# ElectroLab.net
KiCad netlist of a schematic drawn in EAGLE
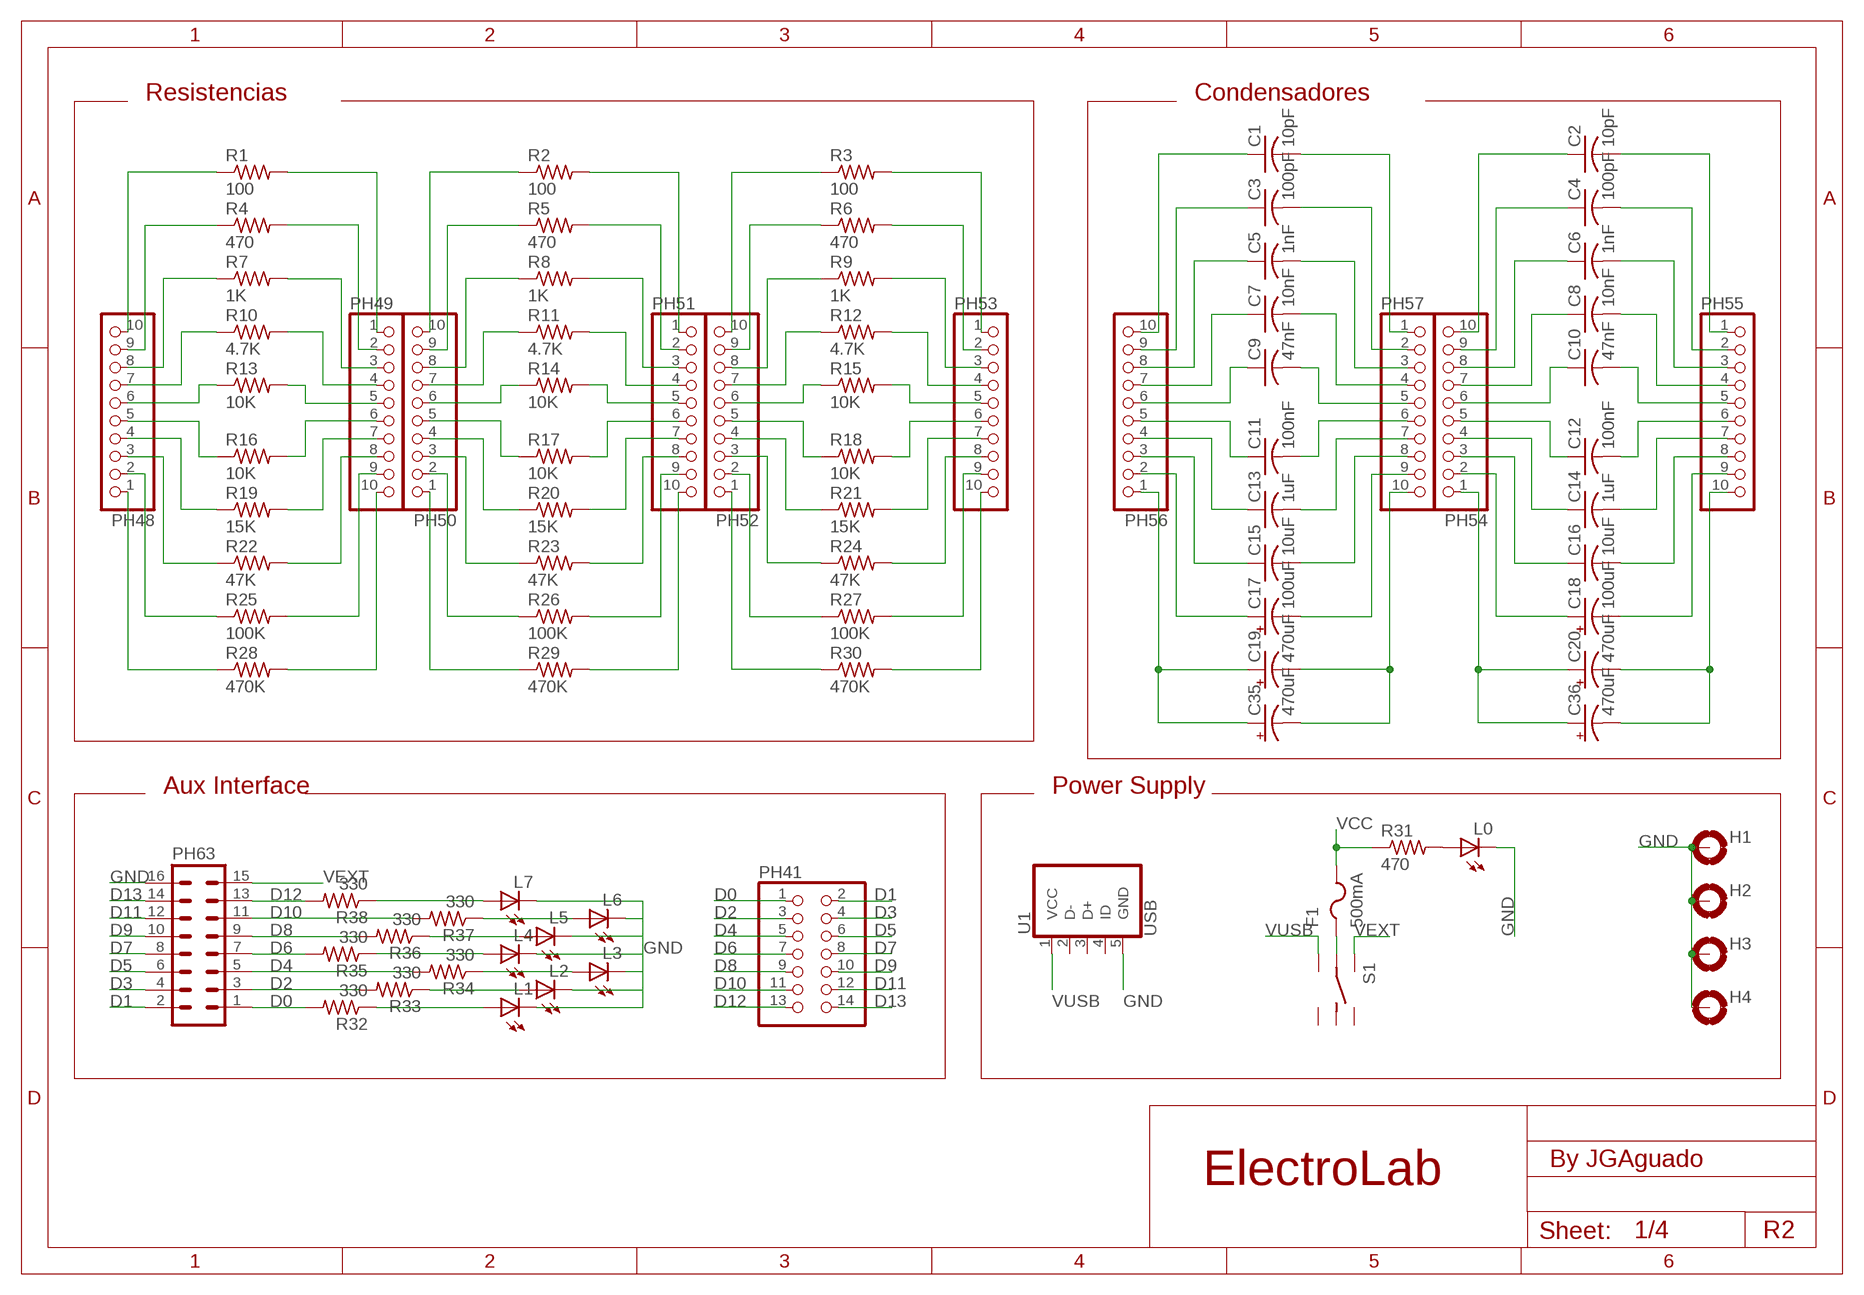
[diagram p0: schematic, sheet 1]
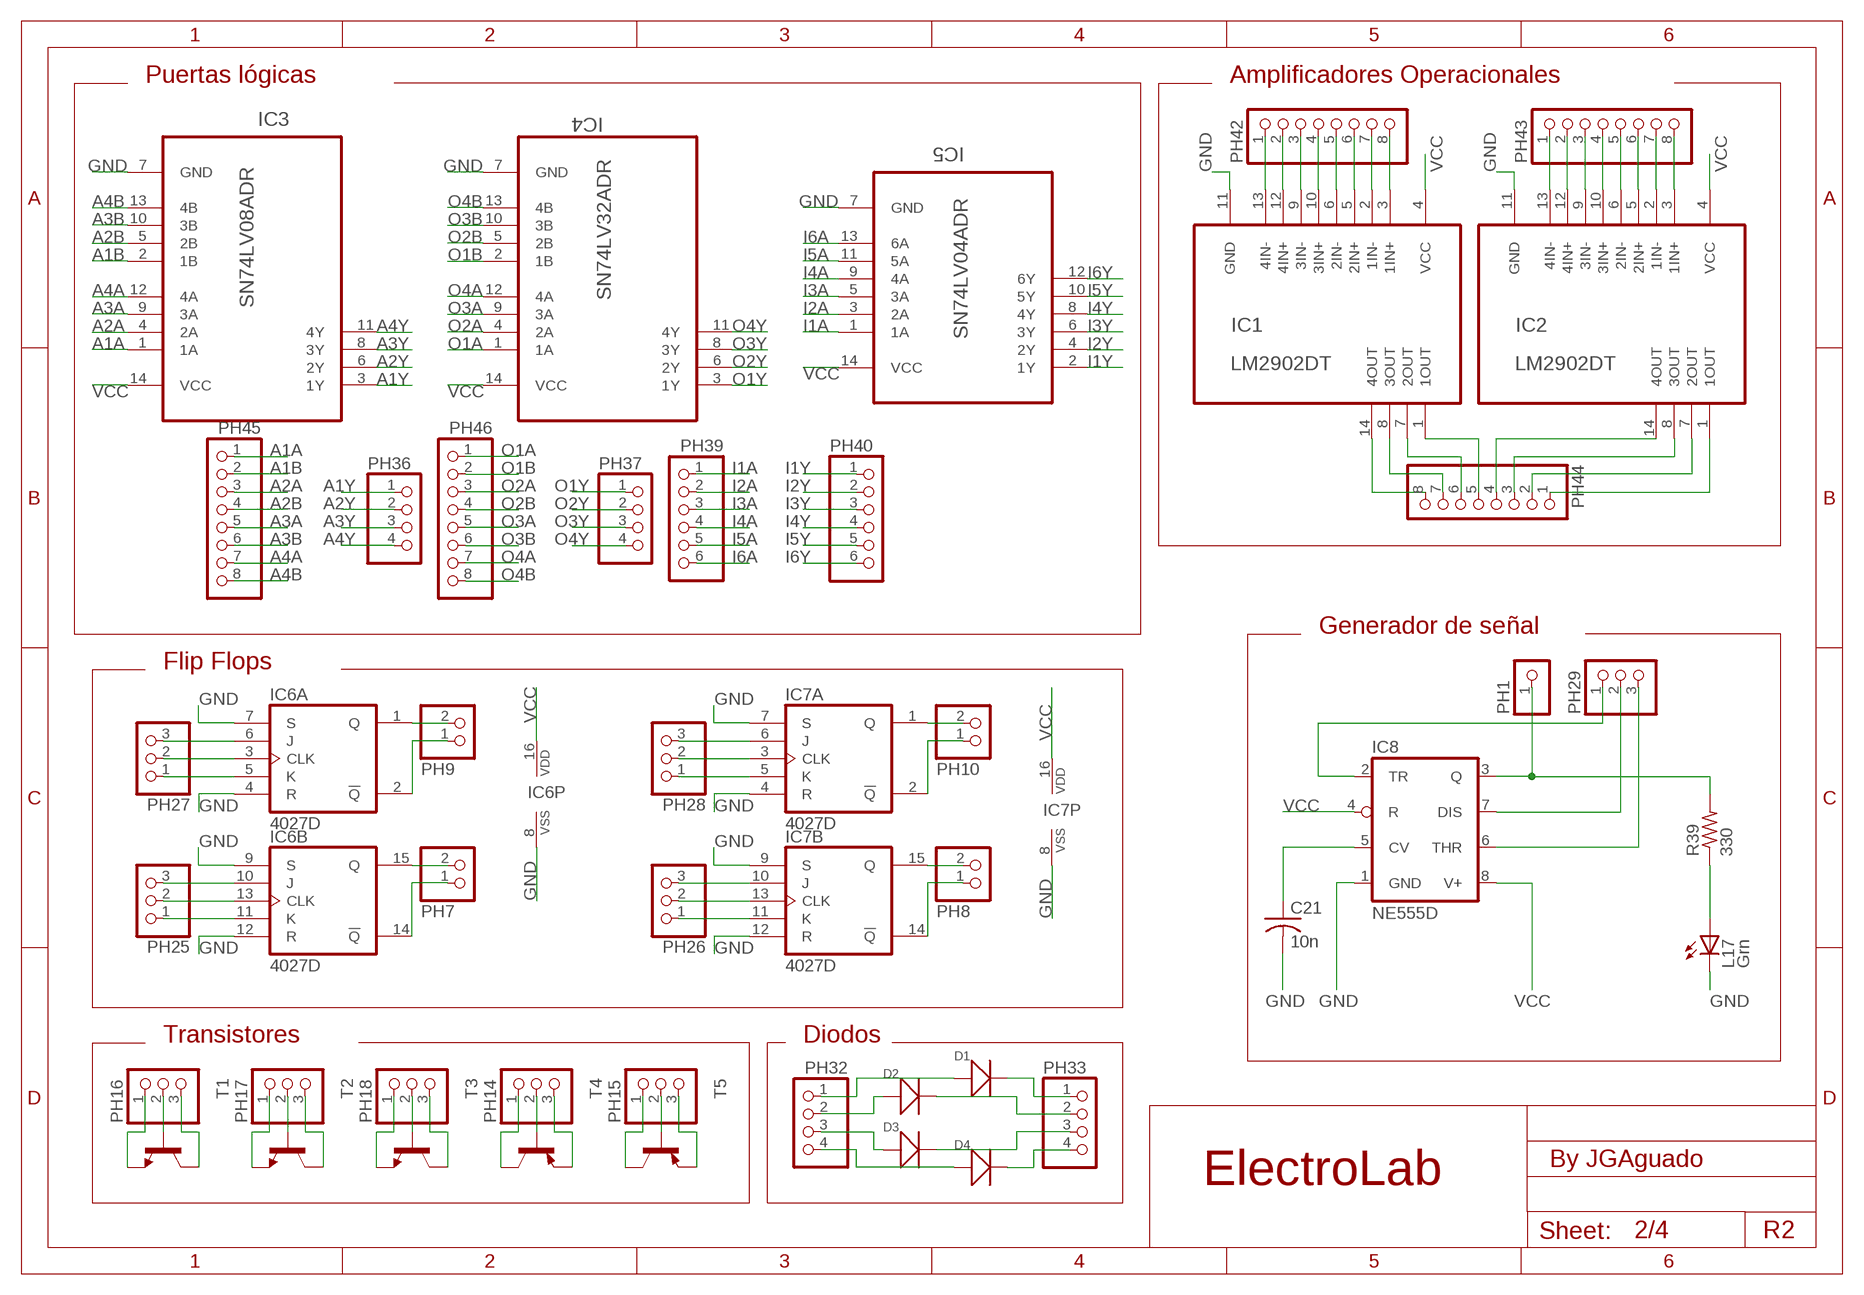
[diagram p1: schematic, sheet 2]
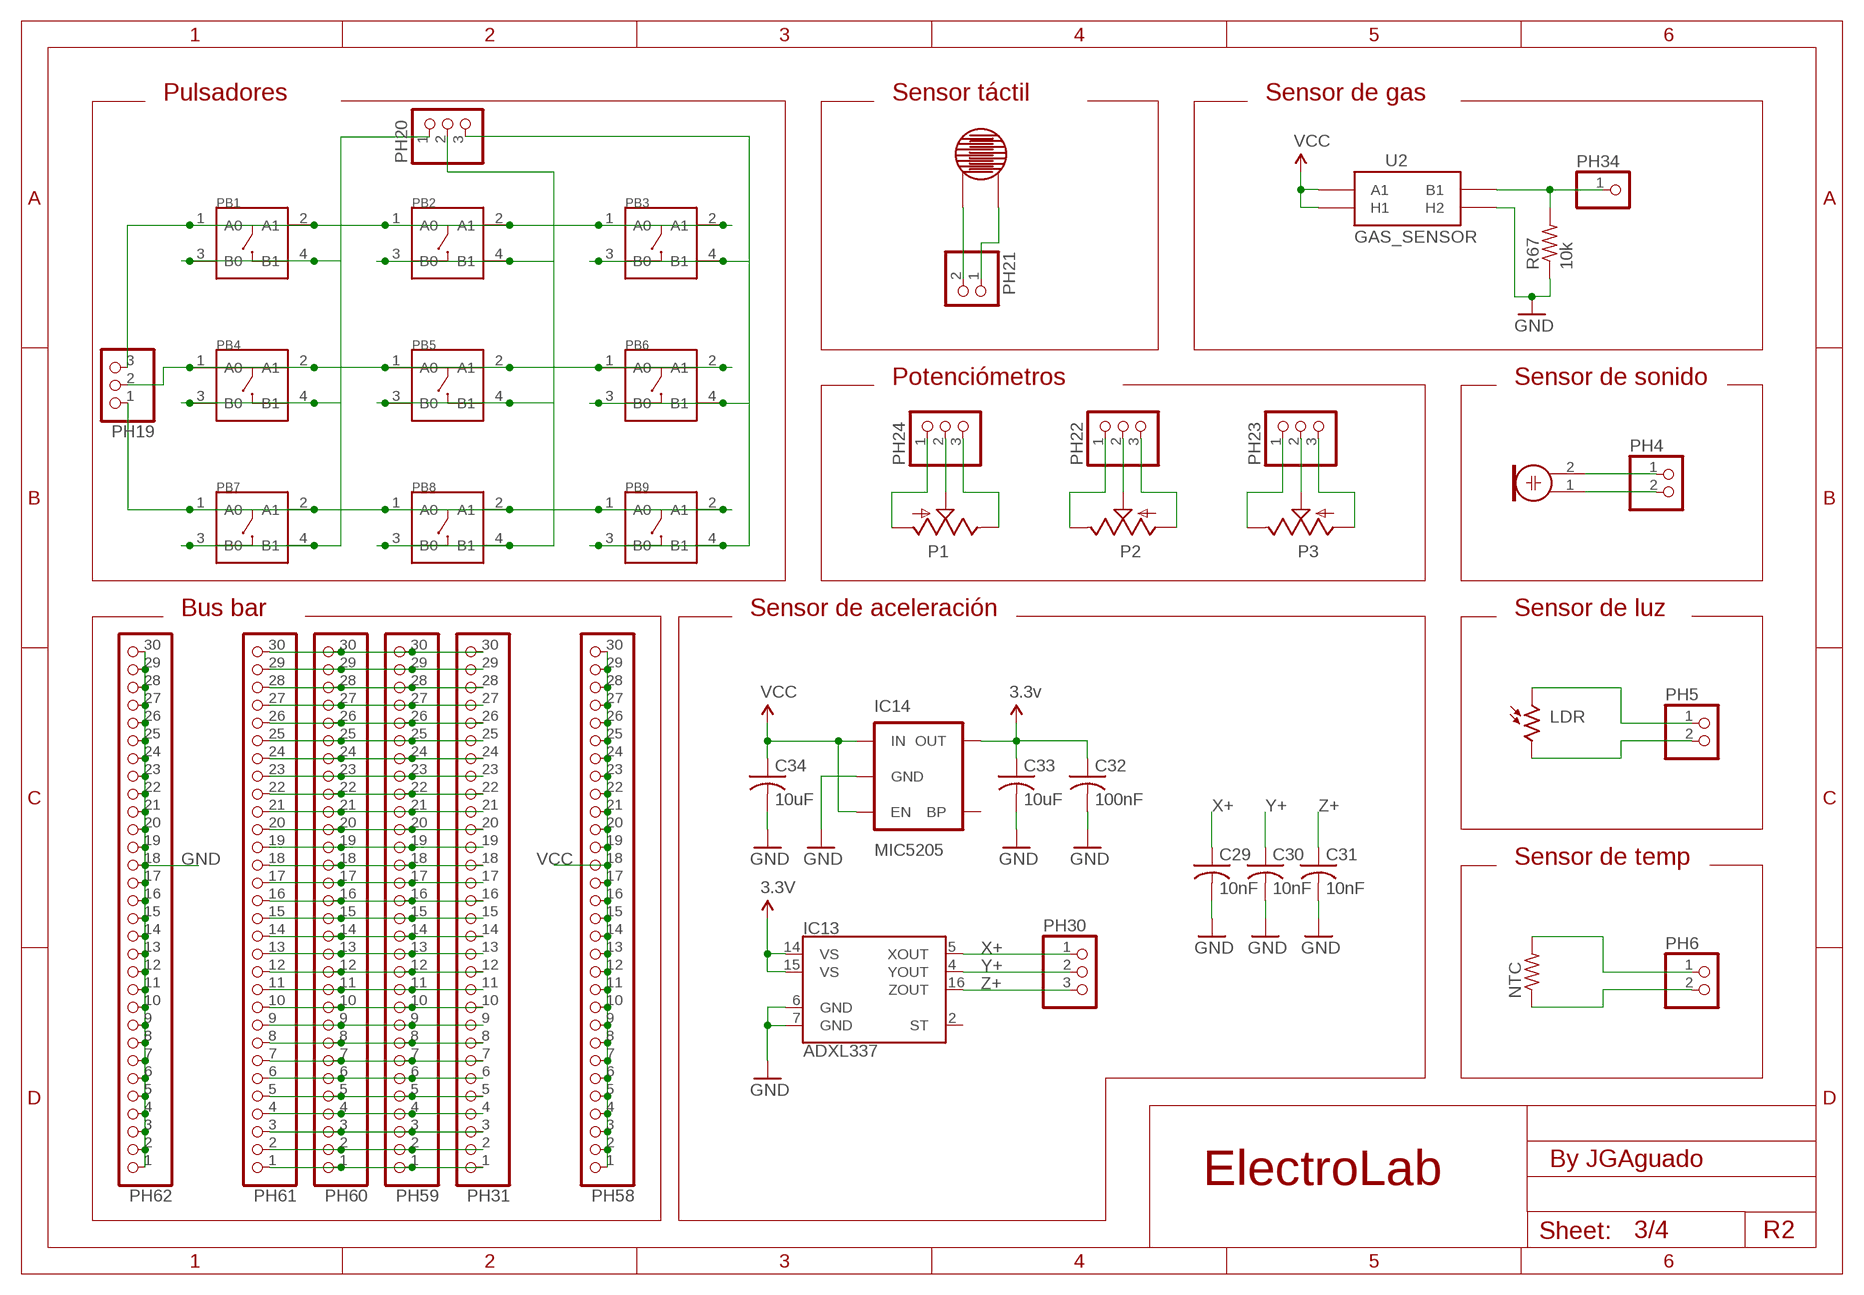
[diagram p2: schematic, sheet 3]
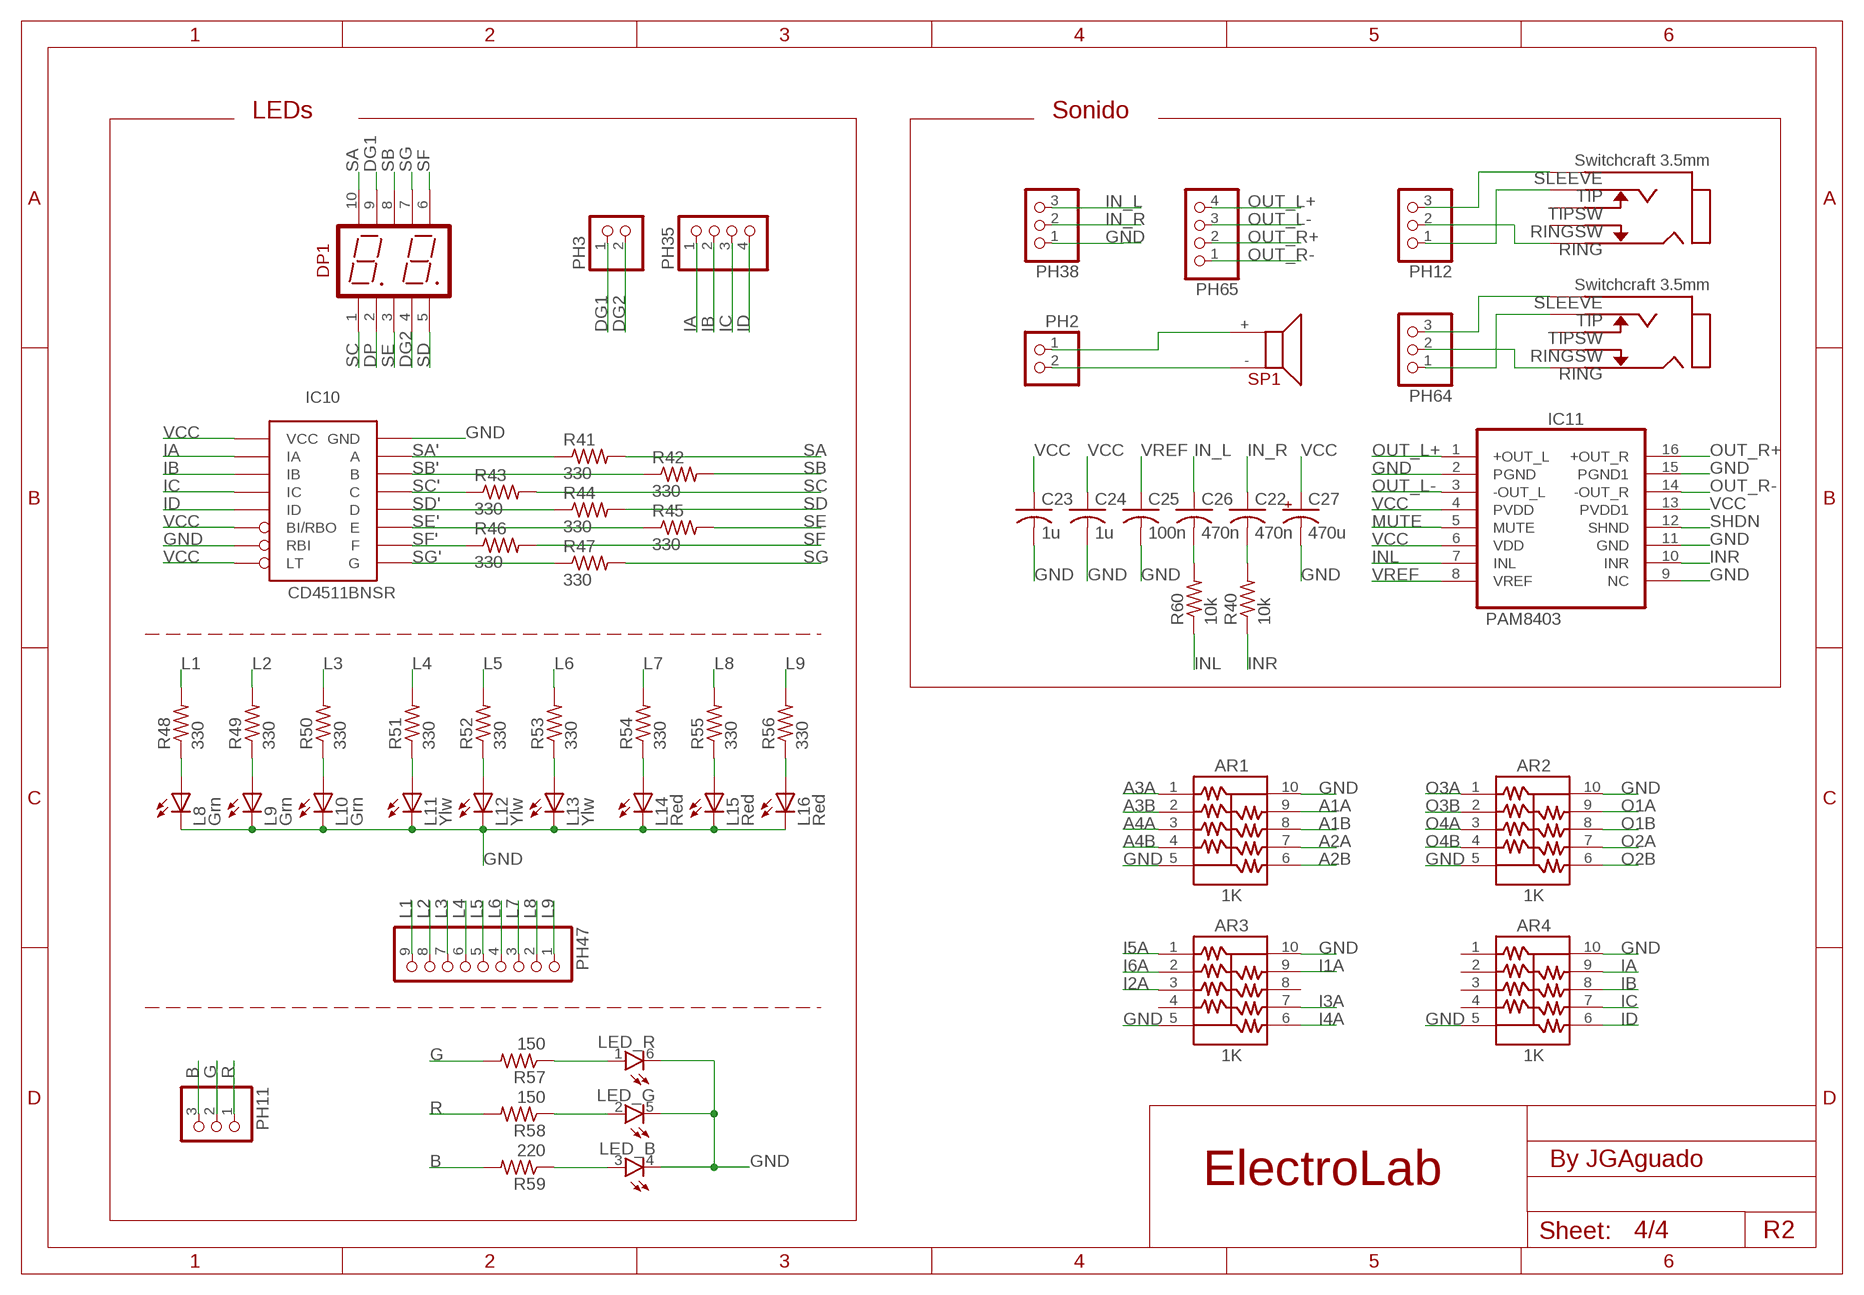
[diagram p3: schematic, sheet 4]

(export (version "E")
  (design (tool "Eeschema 10.0.6"))
  (components
    (comp (ref "C21")
      (value "10n")
      (footprint "eagle-import:0603")
      (libsource (lib "eagle-import") (part "C0603"))
    )
    (comp (ref "D1")
      (value "SMD-DIODE-SWITCHING-75V-150MA(D1206)")
      (footprint "eagle-import:LED-1206")
      (fields (field (name "MPN") "CD1206-S01575"))
      (libsource (lib "eagle-import") (part "SMD-DIODE-SWITCHING-75V-150MA(D1206)"))
    )
    (comp (ref "D2")
      (value "SMD-DIODE-SWITCHING-75V-150MA(D1206)")
      (footprint "eagle-import:LED-1206")
      (fields (field (name "MPN") "CD1206-S01575"))
      (libsource (lib "eagle-import") (part "SMD-DIODE-SWITCHING-75V-150MA(D1206)"))
    )
    (comp (ref "D3")
      (value "SMD-DIODE-SWITCHING-75V-150MA(D1206)")
      (footprint "eagle-import:LED-1206")
      (fields (field (name "MPN") "CD1206-S01575"))
      (libsource (lib "eagle-import") (part "SMD-DIODE-SWITCHING-75V-150MA(D1206)"))
    )
    (comp (ref "D4")
      (value "SMD-DIODE-SWITCHING-75V-150MA(D1206)")
      (footprint "eagle-import:LED-1206")
      (fields (field (name "MPN") "CD1206-S01575"))
      (libsource (lib "eagle-import") (part "SMD-DIODE-SWITCHING-75V-150MA(D1206)"))
    )
    (comp (ref "IC1")
      (value "LM2902DT")
      (footprint "eagle-import:SOIC127P600X175-14N")
      (libsource (lib "eagle-import") (part "LM2902DT"))
    )
    (comp (ref "IC2")
      (value "LM2902DT")
      (footprint "eagle-import:SOIC127P600X175-14N")
      (libsource (lib "eagle-import") (part "LM2902DT"))
    )
    (comp (ref "IC3")
      (value "SN74LV08ADR")
      (footprint "eagle-import:SOIC127P600X175-14N")
      (fields (field (name "MPN") "SN74LVC08AD"))
      (libsource (lib "eagle-import") (part "SN74LVC08AD"))
    )
    (comp (ref "IC4")
      (value "SN74LV32ADR")
      (footprint "eagle-import:SOIC127P600X175-14N")
      (fields (field (name "MPN") "SN74S32D"))
      (libsource (lib "eagle-import") (part "SN74S32D"))
    )
    (comp (ref "IC5")
      (value "SN74LV04ADR")
      (footprint "eagle-import:SOIC127P600X175-14N")
      (libsource (lib "eagle-import") (part "SN74LV04ADR"))
    )
    (comp (ref "IC6")
      (value "4027D")
      (footprint "eagle-import:SO16")
      (libsource (lib "eagle-import") (part "4027D"))
    )
    (comp (ref "IC7")
      (value "4027D")
      (footprint "eagle-import:SO16")
      (libsource (lib "eagle-import") (part "4027D"))
    )
    (comp (ref "IC8")
      (value "NE555D")
      (footprint "eagle-import:SO08")
      (libsource (lib "eagle-import") (part "555DNE"))
    )
    (comp (ref "L17")
      (value "Grn")
      (footprint "eagle-import:1206")
      (libsource (lib "eagle-import") (part "LEDSMT1206"))
    )
    (comp (ref "PH1")
      (value "PINHD-1X1")
      (footprint "eagle-import:1X01")
      (libsource (lib "eagle-import") (part "PINHD-1X1"))
    )
    (comp (ref "PH7")
      (value "PINHD-1X2")
      (footprint "eagle-import:1X02")
      (libsource (lib "eagle-import") (part "PINHD-1X2"))
    )
    (comp (ref "PH8")
      (value "PINHD-1X2")
      (footprint "eagle-import:1X02")
      (libsource (lib "eagle-import") (part "PINHD-1X2"))
    )
    (comp (ref "PH9")
      (value "PINHD-1X2")
      (footprint "eagle-import:1X02")
      (libsource (lib "eagle-import") (part "PINHD-1X2"))
    )
    (comp (ref "PH10")
      (value "PINHD-1X2")
      (footprint "eagle-import:1X02")
      (libsource (lib "eagle-import") (part "PINHD-1X2"))
    )
    (comp (ref "PH14")
      (value "PINHD-1X3")
      (footprint "eagle-import:1X03")
      (libsource (lib "eagle-import") (part "PINHD-1X3"))
    )
    (comp (ref "PH15")
      (value "PINHD-1X3")
      (footprint "eagle-import:1X03")
      (libsource (lib "eagle-import") (part "PINHD-1X3"))
    )
    (comp (ref "PH16")
      (value "PINHD-1X3")
      (footprint "eagle-import:1X03")
      (libsource (lib "eagle-import") (part "PINHD-1X3"))
    )
    (comp (ref "PH17")
      (value "PINHD-1X3")
      (footprint "eagle-import:1X03")
      (libsource (lib "eagle-import") (part "PINHD-1X3"))
    )
    (comp (ref "PH18")
      (value "PINHD-1X3")
      (footprint "eagle-import:1X03")
      (libsource (lib "eagle-import") (part "PINHD-1X3"))
    )
    (comp (ref "PH25")
      (value "PINHD-1X3")
      (footprint "eagle-import:1X03")
      (libsource (lib "eagle-import") (part "PINHD-1X3"))
    )
    (comp (ref "PH26")
      (value "PINHD-1X3")
      (footprint "eagle-import:1X03")
      (libsource (lib "eagle-import") (part "PINHD-1X3"))
    )
    (comp (ref "PH27")
      (value "PINHD-1X3")
      (footprint "eagle-import:1X03")
      (libsource (lib "eagle-import") (part "PINHD-1X3"))
    )
    (comp (ref "PH28")
      (value "PINHD-1X3")
      (footprint "eagle-import:1X03")
      (libsource (lib "eagle-import") (part "PINHD-1X3"))
    )
    (comp (ref "PH29")
      (value "PINHD-1X3")
      (footprint "eagle-import:1X03")
      (libsource (lib "eagle-import") (part "PINHD-1X3"))
    )
    (comp (ref "PH32")
      (value "PINHD-1X4")
      (footprint "eagle-import:1X04")
      (libsource (lib "eagle-import") (part "PINHD-1X4"))
    )
    (comp (ref "PH33")
      (value "PINHD-1X4")
      (footprint "eagle-import:1X04")
      (libsource (lib "eagle-import") (part "PINHD-1X4"))
    )
    (comp (ref "PH36")
      (value "PINHD-1X4")
      (footprint "eagle-import:1X04")
      (libsource (lib "eagle-import") (part "PINHD-1X4"))
    )
    (comp (ref "PH37")
      (value "PINHD-1X4")
      (footprint "eagle-import:1X04")
      (libsource (lib "eagle-import") (part "PINHD-1X4"))
    )
    (comp (ref "PH39")
      (value "PINHD-1X6")
      (footprint "eagle-import:1X06")
      (libsource (lib "eagle-import") (part "PINHD-1X6"))
    )
    (comp (ref "PH40")
      (value "PINHD-1X6")
      (footprint "eagle-import:1X06")
      (libsource (lib "eagle-import") (part "PINHD-1X6"))
    )
    (comp (ref "PH42")
      (value "PINHD-1X8")
      (footprint "eagle-import:1X08")
      (libsource (lib "eagle-import") (part "PINHD-1X8"))
    )
    (comp (ref "PH43")
      (value "PINHD-1X8")
      (footprint "eagle-import:1X08")
      (libsource (lib "eagle-import") (part "PINHD-1X8"))
    )
    (comp (ref "PH44")
      (value "PINHD-1X8")
      (footprint "eagle-import:1X08")
      (libsource (lib "eagle-import") (part "PINHD-1X8"))
    )
    (comp (ref "PH45")
      (value "PINHD-1X8")
      (footprint "eagle-import:1X08")
      (libsource (lib "eagle-import") (part "PINHD-1X8"))
    )
    (comp (ref "PH46")
      (value "PINHD-1X8")
      (footprint "eagle-import:1X08")
      (libsource (lib "eagle-import") (part "PINHD-1X8"))
    )
    (comp (ref "R39")
      (value "330")
      (footprint "eagle-import:R1206")
      (libsource (lib "eagle-import") (part "resistor_R-US_R1206"))
    )
    (comp (ref "T1")
      (value "BC817-16-NPN-SOT23-BEC")
      (footprint "eagle-import:SOT23-BEC")
      (libsource (lib "eagle-import") (part "-NPN-SOT23-BECBC817-16"))
    )
    (comp (ref "T2")
      (value "BC817-16-NPN-SOT23-BEC")
      (footprint "eagle-import:SOT23-BEC")
      (libsource (lib "eagle-import") (part "-NPN-SOT23-BECBC817-16"))
    )
    (comp (ref "T3")
      (value "BC817-16-NPN-SOT23-BEC")
      (footprint "eagle-import:SOT23-BEC")
      (libsource (lib "eagle-import") (part "-NPN-SOT23-BECBC817-16"))
    )
    (comp (ref "T4")
      (value "-PNP-SOT23-BCE")
      (footprint "eagle-import:SOT23-BCE")
      (libsource (lib "eagle-import") (part "-PNP-SOT23-BCE"))
    )
    (comp (ref "T5")
      (value "-PNP-SOT23-BCE")
      (footprint "eagle-import:SOT23-BCE")
      (libsource (lib "eagle-import") (part "-PNP-SOT23-BCE"))
    )
    (comp (ref "C29")
      (value "10nF")
      (footprint "eagle-import:0603")
      (libsource (lib "eagle-import") (part "C0603"))
    )
    (comp (ref "C30")
      (value "10nF")
      (footprint "eagle-import:0603")
      (libsource (lib "eagle-import") (part "C0603"))
    )
    (comp (ref "C31")
      (value "10nF")
      (footprint "eagle-import:0603")
      (libsource (lib "eagle-import") (part "C0603"))
    )
    (comp (ref "C32")
      (value "100nF")
      (footprint "eagle-import:0603")
      (libsource (lib "eagle-import") (part "C0603"))
    )
    (comp (ref "C33")
      (value "10uF")
      (footprint "eagle-import:0603")
      (libsource (lib "eagle-import") (part "C0603"))
    )
    (comp (ref "C34")
      (value "10uF")
      (footprint "eagle-import:0603")
      (libsource (lib "eagle-import") (part "C0603"))
    )
    (comp (ref "IC13")
      (value "ADXL337")
      (footprint "eagle-import:LFCSP-3X3")
      (libsource (lib "eagle-import") (part "ADXL337"))
    )
    (comp (ref "IC14")
      (value "MIC5205")
      (footprint "eagle-import:SOT23-5")
      (libsource (lib "eagle-import") (part "V_REG_LDOSMD"))
    )
    (comp (ref "LDR")
      (value "V1060_21")
      (footprint "eagle-import:TO-5_V10")
      (libsource (lib "eagle-import") (part "?1060V_21"))
    )
    (comp (ref "MIC")
      (value "ELECTRET_MICROPHON-WM-64PC/64PK")
      (footprint "eagle-import:WM-64PC_64PK")
      (libsource (lib "eagle-import") (part "ELECTRET_MICROPHON-WM-64PC/64PK"))
    )
    (comp (ref "NTC")
      (value "R-US_R1206")
      (footprint "eagle-import:R1206@1")
      (libsource (lib "eagle-import") (part "R-US_R1206"))
    )
    (comp (ref "P1")
      (value "SLIDE_POT_20MM")
      (footprint "eagle-import:SLIDE_POT_20MM")
      (libsource (lib "eagle-import") (part "SLIDE_POT_20MM"))
    )
    (comp (ref "P2")
      (value "ALPS_RK09K_VERTICAL")
      (footprint "eagle-import:ALPS_RK09K_VERTICAL")
      (libsource (lib "eagle-import") (part "ALPS_RK09K_VERTICAL"))
    )
    (comp (ref "P3")
      (value "ALPS_RK09K_VERTICAL")
      (footprint "eagle-import:ALPS_RK09K_VERTICAL")
      (libsource (lib "eagle-import") (part "ALPS_RK09K_VERTICAL"))
    )
    (comp (ref "PB1")
      (value "SMD-SWITCH-TACTILE-SPST-NO/TS-1109(4P-D6.0MM)")
      (footprint "eagle-import:SW4-SMD-6.0X6.0X5.0MM")
      (fields (field (name "MPN") "TS-1109"))
      (libsource (lib "eagle-import") (part "SMD-SWITCH-TACTILE-SPST-NO/TS-1109(4P-D6.0MM)"))
    )
    (comp (ref "PB2")
      (value "SMD-SWITCH-TACTILE-SPST-NO/TS-1109(4P-D6.0MM)")
      (footprint "eagle-import:SW4-SMD-6.0X6.0X5.0MM")
      (fields (field (name "MPN") "TS-1109"))
      (libsource (lib "eagle-import") (part "SMD-SWITCH-TACTILE-SPST-NO/TS-1109(4P-D6.0MM)"))
    )
    (comp (ref "PB3")
      (value "SMD-SWITCH-TACTILE-SPST-NO/TS-1109(4P-D6.0MM)")
      (footprint "eagle-import:SW4-SMD-6.0X6.0X5.0MM")
      (fields (field (name "MPN") "TS-1109"))
      (libsource (lib "eagle-import") (part "SMD-SWITCH-TACTILE-SPST-NO/TS-1109(4P-D6.0MM)"))
    )
    (comp (ref "PB4")
      (value "SMD-SWITCH-TACTILE-SPST-NO/TS-1109(4P-D6.0MM)")
      (footprint "eagle-import:SW4-SMD-6.0X6.0X5.0MM")
      (fields (field (name "MPN") "TS-1109"))
      (libsource (lib "eagle-import") (part "SMD-SWITCH-TACTILE-SPST-NO/TS-1109(4P-D6.0MM)"))
    )
    (comp (ref "PB5")
      (value "SMD-SWITCH-TACTILE-SPST-NO/TS-1109(4P-D6.0MM)")
      (footprint "eagle-import:SW4-SMD-6.0X6.0X5.0MM")
      (fields (field (name "MPN") "TS-1109"))
      (libsource (lib "eagle-import") (part "SMD-SWITCH-TACTILE-SPST-NO/TS-1109(4P-D6.0MM)"))
    )
    (comp (ref "PB6")
      (value "SMD-SWITCH-TACTILE-SPST-NO/TS-1109(4P-D6.0MM)")
      (footprint "eagle-import:SW4-SMD-6.0X6.0X5.0MM")
      (fields (field (name "MPN") "TS-1109"))
      (libsource (lib "eagle-import") (part "SMD-SWITCH-TACTILE-SPST-NO/TS-1109(4P-D6.0MM)"))
    )
    (comp (ref "PB7")
      (value "SMD-SWITCH-TACTILE-SPST-NO/TS-1109(4P-D6.0MM)")
      (footprint "eagle-import:SW4-SMD-6.0X6.0X5.0MM")
      (fields (field (name "MPN") "TS-1109"))
      (libsource (lib "eagle-import") (part "SMD-SWITCH-TACTILE-SPST-NO/TS-1109(4P-D6.0MM)"))
    )
    (comp (ref "PB8")
      (value "SMD-SWITCH-TACTILE-SPST-NO/TS-1109(4P-D6.0MM)")
      (footprint "eagle-import:SW4-SMD-6.0X6.0X5.0MM")
      (fields (field (name "MPN") "TS-1109"))
      (libsource (lib "eagle-import") (part "SMD-SWITCH-TACTILE-SPST-NO/TS-1109(4P-D6.0MM)"))
    )
    (comp (ref "PB9")
      (value "SMD-SWITCH-TACTILE-SPST-NO/TS-1109(4P-D6.0MM)")
      (footprint "eagle-import:SW4-SMD-6.0X6.0X5.0MM")
      (fields (field (name "MPN") "TS-1109"))
      (libsource (lib "eagle-import") (part "SMD-SWITCH-TACTILE-SPST-NO/TS-1109(4P-D6.0MM)"))
    )
    (comp (ref "PH4")
      (value "PINHD-1X2")
      (footprint "eagle-import:1X02")
      (libsource (lib "eagle-import") (part "PINHD-1X2"))
    )
    (comp (ref "PH5")
      (value "PINHD-1X2")
      (footprint "eagle-import:1X02")
      (libsource (lib "eagle-import") (part "PINHD-1X2"))
    )
    (comp (ref "PH6")
      (value "PINHD-1X2")
      (footprint "eagle-import:1X02")
      (libsource (lib "eagle-import") (part "PINHD-1X2"))
    )
    (comp (ref "PH19")
      (value "PINHD-1X3")
      (footprint "eagle-import:1X03")
      (libsource (lib "eagle-import") (part "PINHD-1X3"))
    )
    (comp (ref "PH20")
      (value "PINHD-1X3")
      (footprint "eagle-import:1X03")
      (libsource (lib "eagle-import") (part "PINHD-1X3"))
    )
    (comp (ref "PH21")
      (value "PINHD-1X2")
      (footprint "eagle-import:1X02")
      (libsource (lib "eagle-import") (part "PINHD-1X2"))
    )
    (comp (ref "PH22")
      (value "PINHD-1X3")
      (footprint "eagle-import:1X03")
      (libsource (lib "eagle-import") (part "PINHD-1X3"))
    )
    (comp (ref "PH23")
      (value "PINHD-1X3")
      (footprint "eagle-import:1X03")
      (libsource (lib "eagle-import") (part "PINHD-1X3"))
    )
    (comp (ref "PH24")
      (value "PINHD-1X3")
      (footprint "eagle-import:1X03")
      (libsource (lib "eagle-import") (part "PINHD-1X3"))
    )
    (comp (ref "PH30")
      (value "PINHD-1X3")
      (footprint "eagle-import:1X03")
      (libsource (lib "eagle-import") (part "PINHD-1X3"))
    )
    (comp (ref "PH31")
      (value "PINHD-1X30")
      (footprint "eagle-import:1X30")
      (libsource (lib "eagle-import") (part "PINHD-1X30"))
    )
    (comp (ref "PH34")
      (value "PINHD-1X1")
      (footprint "eagle-import:1X01")
      (libsource (lib "eagle-import") (part "PINHD-1X1"))
    )
    (comp (ref "PH58")
      (value "PINHD-1X30")
      (footprint "eagle-import:1X30")
      (libsource (lib "eagle-import") (part "PINHD-1X30"))
    )
    (comp (ref "PH59")
      (value "PINHD-1X30")
      (footprint "eagle-import:1X30")
      (libsource (lib "eagle-import") (part "PINHD-1X30"))
    )
    (comp (ref "PH60")
      (value "PINHD-1X30")
      (footprint "eagle-import:1X30")
      (libsource (lib "eagle-import") (part "PINHD-1X30"))
    )
    (comp (ref "PH61")
      (value "PINHD-1X30")
      (footprint "eagle-import:1X30")
      (libsource (lib "eagle-import") (part "PINHD-1X30"))
    )
    (comp (ref "PH62")
      (value "PINHD-1X30")
      (footprint "eagle-import:1X30")
      (libsource (lib "eagle-import") (part "PINHD-1X30"))
    )
    (comp (ref "R67")
      (value "10k")
      (footprint "eagle-import:0603")
      (libsource (lib "eagle-import") (part "R0603"))
    )
    (comp (ref "U$16")
      (value "RESISTIVE_SENSOR_PAD")
      (footprint "eagle-import:RESISTIVE_SENSOR_PAD")
      (libsource (lib "eagle-import") (part "RESISTIVE_SENSOR_PAD"))
    )
    (comp (ref "U2")
      (value "GAS_SENSOR")
      (footprint "eagle-import:MQ-3")
      (libsource (lib "eagle-import") (part "GAS_SENSOR"))
    )
    (comp (ref "AR1")
      (value "1K")
      (footprint "eagle-import:RESISTOR_ARRAY_X8_CAY17")
      (libsource (lib "eagle-import") (part "RESISTOR_ARRAY_X8_CAY17"))
    )
    (comp (ref "AR2")
      (value "1K")
      (footprint "eagle-import:RESISTOR_ARRAY_X8_CAY17")
      (libsource (lib "eagle-import") (part "RESISTOR_ARRAY_X8_CAY17"))
    )
    (comp (ref "AR3")
      (value "1K")
      (footprint "eagle-import:RESISTOR_ARRAY_X8_CAY17")
      (libsource (lib "eagle-import") (part "RESISTOR_ARRAY_X8_CAY17"))
    )
    (comp (ref "AR4")
      (value "1K")
      (footprint "eagle-import:RESISTOR_ARRAY_X8_CAY17")
      (libsource (lib "eagle-import") (part "RESISTOR_ARRAY_X8_CAY17"))
    )
    (comp (ref "C22")
      (value "470n")
      (footprint "eagle-import:0603")
      (libsource (lib "eagle-import") (part "C0603"))
    )
    (comp (ref "C23")
      (value "1u")
      (footprint "eagle-import:0603")
      (libsource (lib "eagle-import") (part "C0603"))
    )
    (comp (ref "C24")
      (value "1u")
      (footprint "eagle-import:0603")
      (libsource (lib "eagle-import") (part "C0603"))
    )
    (comp (ref "C25")
      (value "100n")
      (footprint "eagle-import:0603")
      (libsource (lib "eagle-import") (part "C0603"))
    )
    (comp (ref "C26")
      (value "470n")
      (footprint "eagle-import:0603")
      (libsource (lib "eagle-import") (part "C0603"))
    )
    (comp (ref "C27")
      (value "470u")
      (footprint "eagle-import:D_7343-31W")
      (libsource (lib "eagle-import") (part "CPOL-USD/7343-31W"))
    )
    (comp (ref "DP1")
      (value "2X7_SEGMENT_COMMON_CATODE_12_PINS")
      (footprint "eagle-import:2X7_SEGMENT_COMMON_CATODE_12_PINS")
      (libsource (lib "eagle-import") (part "2X7_SEGMENT_COMMON_CATODE_12_PINS"))
    )
    (comp (ref "IC10")
      (value "CD4511BNSR")
      (footprint "eagle-import:SN74LS247D")
      (libsource (lib "eagle-import") (part "SN74LS247D"))
    )
    (comp (ref "IC11")
      (value "PAM8403")
      (footprint "eagle-import:SOP-16")
      (libsource (lib "eagle-import") (part "PAM8403"))
    )
    (comp (ref "JC1")
      (value "SWTCHCRFT_3.5JACK5-JACK-SMD")
      (footprint "eagle-import:4-JACK-SMD")
      (libsource (lib "eagle-import") (part "SWTCHCRFT_3.5JACK5-JACK-SMD"))
    )
    (comp (ref "JC2")
      (value "SWTCHCRFT_3.5JACK5-JACK-SMD")
      (footprint "eagle-import:4-JACK-SMD")
      (libsource (lib "eagle-import") (part "SWTCHCRFT_3.5JACK5-JACK-SMD"))
    )
    (comp (ref "L8")
      (value "Grn")
      (footprint "eagle-import:1206")
      (libsource (lib "eagle-import") (part "LEDSMT1206"))
    )
    (comp (ref "L9")
      (value "Grn")
      (footprint "eagle-import:1206")
      (libsource (lib "eagle-import") (part "LEDSMT1206"))
    )
    (comp (ref "L10")
      (value "Grn")
      (footprint "eagle-import:1206")
      (libsource (lib "eagle-import") (part "LEDSMT1206"))
    )
    (comp (ref "L11")
      (value "Ylw")
      (footprint "eagle-import:1206")
      (libsource (lib "eagle-import") (part "LEDSMT1206"))
    )
    (comp (ref "L12")
      (value "Ylw")
      (footprint "eagle-import:1206")
      (libsource (lib "eagle-import") (part "LEDSMT1206"))
    )
    (comp (ref "L13")
      (value "Ylw")
      (footprint "eagle-import:1206")
      (libsource (lib "eagle-import") (part "LEDSMT1206"))
    )
    (comp (ref "L14")
      (value "Red")
      (footprint "eagle-import:1206")
      (libsource (lib "eagle-import") (part "LEDSMT1206"))
    )
    (comp (ref "L15")
      (value "Red")
      (footprint "eagle-import:1206")
      (libsource (lib "eagle-import") (part "LEDSMT1206"))
    )
    (comp (ref "L16")
      (value "Red")
      (footprint "eagle-import:1206")
      (libsource (lib "eagle-import") (part "LEDSMT1206"))
    )
    (comp (ref "LED_")
      (value "LED_RGB_PLCC-6")
      (footprint "eagle-import:PLCC-6")
      (libsource (lib "eagle-import") (part "LED_RGB_PLCC-6"))
    )
    (comp (ref "PH2")
      (value "PINHD-1X2")
      (footprint "eagle-import:1X02")
      (libsource (lib "eagle-import") (part "PINHD-1X2"))
    )
    (comp (ref "PH3")
      (value "PINHD-1X2")
      (footprint "eagle-import:1X02")
      (libsource (lib "eagle-import") (part "PINHD-1X2"))
    )
    (comp (ref "PH11")
      (value "PINHD-1X3")
      (footprint "eagle-import:1X03")
      (libsource (lib "eagle-import") (part "PINHD-1X3"))
    )
    (comp (ref "PH12")
      (value "PINHD-1X3")
      (footprint "eagle-import:1X03")
      (libsource (lib "eagle-import") (part "PINHD-1X3"))
    )
    (comp (ref "PH35")
      (value "PINHD-1X4")
      (footprint "eagle-import:1X04")
      (libsource (lib "eagle-import") (part "PINHD-1X4"))
    )
    (comp (ref "PH38")
      (value "PINHD-1X3")
      (footprint "eagle-import:1X03")
      (libsource (lib "eagle-import") (part "PINHD-1X3"))
    )
    (comp (ref "PH47")
      (value "PINHD-1X9")
      (footprint "eagle-import:1X09")
      (libsource (lib "eagle-import") (part "PINHD-1X9"))
    )
    (comp (ref "PH64")
      (value "PINHD-1X3")
      (footprint "eagle-import:1X03")
      (libsource (lib "eagle-import") (part "PINHD-1X3"))
    )
    (comp (ref "PH65")
      (value "PINHD-1X4")
      (footprint "eagle-import:1X04")
      (libsource (lib "eagle-import") (part "PINHD-1X4"))
    )
    (comp (ref "R40")
      (value "10k")
      (footprint "eagle-import:0603")
      (libsource (lib "eagle-import") (part "R0603"))
    )
    (comp (ref "R41")
      (value "330")
      (footprint "eagle-import:R1206")
      (libsource (lib "eagle-import") (part "resistor_R-US_R1206"))
    )
    (comp (ref "R42")
      (value "330")
      (footprint "eagle-import:R1206")
      (libsource (lib "eagle-import") (part "resistor_R-US_R1206"))
    )
    (comp (ref "R43")
      (value "330")
      (footprint "eagle-import:R1206")
      (libsource (lib "eagle-import") (part "resistor_R-US_R1206"))
    )
    (comp (ref "R44")
      (value "330")
      (footprint "eagle-import:R1206")
      (libsource (lib "eagle-import") (part "resistor_R-US_R1206"))
    )
    (comp (ref "R45")
      (value "330")
      (footprint "eagle-import:R1206")
      (libsource (lib "eagle-import") (part "resistor_R-US_R1206"))
    )
    (comp (ref "R46")
      (value "330")
      (footprint "eagle-import:R1206")
      (libsource (lib "eagle-import") (part "resistor_R-US_R1206"))
    )
    (comp (ref "R47")
      (value "330")
      (footprint "eagle-import:R1206")
      (libsource (lib "eagle-import") (part "resistor_R-US_R1206"))
    )
    (comp (ref "R48")
      (value "330")
      (footprint "eagle-import:R1206")
      (libsource (lib "eagle-import") (part "resistor_R-US_R1206"))
    )
    (comp (ref "R49")
      (value "330")
      (footprint "eagle-import:R1206")
      (libsource (lib "eagle-import") (part "resistor_R-US_R1206"))
    )
    (comp (ref "R50")
      (value "330")
      (footprint "eagle-import:R1206")
      (libsource (lib "eagle-import") (part "resistor_R-US_R1206"))
    )
    (comp (ref "R51")
      (value "330")
      (footprint "eagle-import:R1206")
      (libsource (lib "eagle-import") (part "resistor_R-US_R1206"))
    )
    (comp (ref "R52")
      (value "330")
      (footprint "eagle-import:R1206")
      (libsource (lib "eagle-import") (part "resistor_R-US_R1206"))
    )
    (comp (ref "R53")
      (value "330")
      (footprint "eagle-import:R1206")
      (libsource (lib "eagle-import") (part "resistor_R-US_R1206"))
    )
    (comp (ref "R54")
      (value "330")
      (footprint "eagle-import:R1206")
      (libsource (lib "eagle-import") (part "resistor_R-US_R1206"))
    )
    (comp (ref "R55")
      (value "330")
      (footprint "eagle-import:R1206")
      (libsource (lib "eagle-import") (part "resistor_R-US_R1206"))
    )
    (comp (ref "R56")
      (value "330")
      (footprint "eagle-import:R1206")
      (libsource (lib "eagle-import") (part "resistor_R-US_R1206"))
    )
    (comp (ref "R57")
      (value "150")
      (footprint "eagle-import:R1206")
      (libsource (lib "eagle-import") (part "resistor_R-US_R1206"))
    )
    (comp (ref "R58")
      (value "150")
      (footprint "eagle-import:R1206")
      (libsource (lib "eagle-import") (part "resistor_R-US_R1206"))
    )
    (comp (ref "R59")
      (value "220")
      (footprint "eagle-import:R1206")
      (libsource (lib "eagle-import") (part "resistor_R-US_R1206"))
    )
    (comp (ref "R60")
      (value "10k")
      (footprint "eagle-import:0603")
      (libsource (lib "eagle-import") (part "R0603"))
    )
    (comp (ref "SP1")
      (value "32MM_SPEAKER")
      (footprint "eagle-import:32MM_SPEAKER")
      (libsource (lib "eagle-import") (part "32MM_SPEAKER"))
    )
    (comp (ref "C1")
      (value "10pF")
      (footprint "eagle-import:C1206")
      (libsource (lib "eagle-import") (part "C-USC1206"))
    )
    (comp (ref "C2")
      (value "10pF")
      (footprint "eagle-import:C1206")
      (libsource (lib "eagle-import") (part "C-USC1206"))
    )
    (comp (ref "C3")
      (value "100pF")
      (footprint "eagle-import:C1206")
      (libsource (lib "eagle-import") (part "C-USC1206"))
    )
    (comp (ref "C4")
      (value "100pF")
      (footprint "eagle-import:C1206")
      (libsource (lib "eagle-import") (part "C-USC1206"))
    )
    (comp (ref "C5")
      (value "1nF")
      (footprint "eagle-import:C1206")
      (libsource (lib "eagle-import") (part "C-USC1206"))
    )
    (comp (ref "C6")
      (value "1nF")
      (footprint "eagle-import:C1206")
      (libsource (lib "eagle-import") (part "C-USC1206"))
    )
    (comp (ref "C7")
      (value "10nF")
      (footprint "eagle-import:C1206")
      (libsource (lib "eagle-import") (part "C-USC1206"))
    )
    (comp (ref "C8")
      (value "10nF")
      (footprint "eagle-import:C1206")
      (libsource (lib "eagle-import") (part "C-USC1206"))
    )
    (comp (ref "C9")
      (value "47nF")
      (footprint "eagle-import:C1206")
      (libsource (lib "eagle-import") (part "C-USC1206"))
    )
    (comp (ref "C10")
      (value "47nF")
      (footprint "eagle-import:C1206")
      (libsource (lib "eagle-import") (part "C-USC1206"))
    )
    (comp (ref "C11")
      (value "100nF")
      (footprint "eagle-import:C1206")
      (libsource (lib "eagle-import") (part "C-USC1206"))
    )
    (comp (ref "C12")
      (value "100nF")
      (footprint "eagle-import:C1206")
      (libsource (lib "eagle-import") (part "C-USC1206"))
    )
    (comp (ref "C13")
      (value "1uF")
      (footprint "eagle-import:C1206")
      (libsource (lib "eagle-import") (part "C-USC1206"))
    )
    (comp (ref "C14")
      (value "1uF")
      (footprint "eagle-import:C1206")
      (libsource (lib "eagle-import") (part "C-USC1206"))
    )
    (comp (ref "C15")
      (value "10uF")
      (footprint "eagle-import:C1206")
      (libsource (lib "eagle-import") (part "C-USC1206"))
    )
    (comp (ref "C16")
      (value "10uF")
      (footprint "eagle-import:C1206")
      (libsource (lib "eagle-import") (part "C-USC1206"))
    )
    (comp (ref "C17")
      (value "100uF")
      (footprint "eagle-import:A_3216-18R")
      (libsource (lib "eagle-import") (part "CPOL-USA/3216-18R"))
    )
    (comp (ref "C18")
      (value "100uF")
      (footprint "eagle-import:A_3216-18R")
      (libsource (lib "eagle-import") (part "CPOL-USA/3216-18R"))
    )
    (comp (ref "C19")
      (value "470uF")
      (footprint "eagle-import:D_7343-31R")
      (libsource (lib "eagle-import") (part "CPOL-USD/7343-31R"))
    )
    (comp (ref "C20")
      (value "470uF")
      (footprint "eagle-import:D_7343-31R")
      (libsource (lib "eagle-import") (part "CPOL-USD/7343-31R"))
    )
    (comp (ref "C35")
      (value "470uF")
      (footprint "eagle-import:D_7343-31R")
      (libsource (lib "eagle-import") (part "CPOL-USD/7343-31R"))
    )
    (comp (ref "C36")
      (value "470uF")
      (footprint "eagle-import:D_7343-31R")
      (libsource (lib "eagle-import") (part "CPOL-USD/7343-31R"))
    )
    (comp (ref "F1")
      (value "500mA")
      (footprint "eagle-import:R1206")
      (libsource (lib "eagle-import") (part "PTCFUSE-1206"))
    )
    (comp (ref "H1")
      (value "MOUNT-PAD-ROUND2.8")
      (footprint "eagle-import:2,8-PAD")
      (libsource (lib "eagle-import") (part "MOUNT-PAD-ROUND2.8"))
    )
    (comp (ref "H2")
      (value "MOUNT-PAD-ROUND2.8")
      (footprint "eagle-import:2,8-PAD")
      (libsource (lib "eagle-import") (part "MOUNT-PAD-ROUND2.8"))
    )
    (comp (ref "H3")
      (value "MOUNT-PAD-ROUND2.8")
      (footprint "eagle-import:2,8-PAD")
      (libsource (lib "eagle-import") (part "MOUNT-PAD-ROUND2.8"))
    )
    (comp (ref "H4")
      (value "MOUNT-PAD-ROUND2.8")
      (footprint "eagle-import:2,8-PAD")
      (libsource (lib "eagle-import") (part "MOUNT-PAD-ROUND2.8"))
    )
    (comp (ref "L0")
      (value "LEDSMT1206")
      (footprint "eagle-import:1206")
      (libsource (lib "eagle-import") (part "LEDSMT1206"))
    )
    (comp (ref "L1")
      (value "LEDSMT1206")
      (footprint "eagle-import:1206")
      (libsource (lib "eagle-import") (part "LEDSMT1206"))
    )
    (comp (ref "L2")
      (value "LEDSMT1206")
      (footprint "eagle-import:1206")
      (libsource (lib "eagle-import") (part "LEDSMT1206"))
    )
    (comp (ref "L3")
      (value "LEDSMT1206")
      (footprint "eagle-import:1206")
      (libsource (lib "eagle-import") (part "LEDSMT1206"))
    )
    (comp (ref "L4")
      (value "LEDSMT1206")
      (footprint "eagle-import:1206")
      (libsource (lib "eagle-import") (part "LEDSMT1206"))
    )
    (comp (ref "L5")
      (value "LEDSMT1206")
      (footprint "eagle-import:1206")
      (libsource (lib "eagle-import") (part "LEDSMT1206"))
    )
    (comp (ref "L6")
      (value "LEDSMT1206")
      (footprint "eagle-import:1206")
      (libsource (lib "eagle-import") (part "LEDSMT1206"))
    )
    (comp (ref "L7")
      (value "LEDSMT1206")
      (footprint "eagle-import:1206")
      (libsource (lib "eagle-import") (part "LEDSMT1206"))
    )
    (comp (ref "PH41")
      (value "PINHD-2X7")
      (footprint "eagle-import:2X07")
      (libsource (lib "eagle-import") (part "PINHD-2X7"))
    )
    (comp (ref "PH48")
      (value "PINHD-1X10")
      (footprint "eagle-import:1X10-BIG")
      (libsource (lib "eagle-import") (part "PINHD-1X10"))
    )
    (comp (ref "PH49")
      (value "PINHD-1X10")
      (footprint "eagle-import:1X10-BIG")
      (libsource (lib "eagle-import") (part "PINHD-1X10"))
    )
    (comp (ref "PH50")
      (value "PINHD-1X10")
      (footprint "eagle-import:1X10-BIG")
      (libsource (lib "eagle-import") (part "PINHD-1X10"))
    )
    (comp (ref "PH51")
      (value "PINHD-1X10")
      (footprint "eagle-import:1X10-BIG")
      (libsource (lib "eagle-import") (part "PINHD-1X10"))
    )
    (comp (ref "PH52")
      (value "PINHD-1X10")
      (footprint "eagle-import:1X10-BIG")
      (libsource (lib "eagle-import") (part "PINHD-1X10"))
    )
    (comp (ref "PH53")
      (value "PINHD-1X10")
      (footprint "eagle-import:1X10-BIG")
      (libsource (lib "eagle-import") (part "PINHD-1X10"))
    )
    (comp (ref "PH54")
      (value "PINHD-1X10")
      (footprint "eagle-import:1X10-BIG")
      (libsource (lib "eagle-import") (part "PINHD-1X10"))
    )
    (comp (ref "PH55")
      (value "PINHD-1X10")
      (footprint "eagle-import:1X10-BIG")
      (libsource (lib "eagle-import") (part "PINHD-1X10"))
    )
    (comp (ref "PH56")
      (value "PINHD-1X10")
      (footprint "eagle-import:1X10-BIG")
      (libsource (lib "eagle-import") (part "PINHD-1X10"))
    )
    (comp (ref "PH57")
      (value "PINHD-1X10")
      (footprint "eagle-import:1X10-BIG")
      (libsource (lib "eagle-import") (part "PINHD-1X10"))
    )
    (comp (ref "PH63")
      (value "MA08-2")
      (footprint "eagle-import:MA08-2")
      (libsource (lib "eagle-import") (part "MA08-2"))
    )
    (comp (ref "R1")
      (value "100")
      (footprint "eagle-import:R1206")
      (libsource (lib "eagle-import") (part "resistor_R-US_R1206"))
    )
    (comp (ref "R2")
      (value "100")
      (footprint "eagle-import:R1206")
      (libsource (lib "eagle-import") (part "resistor_R-US_R1206"))
    )
    (comp (ref "R3")
      (value "100")
      (footprint "eagle-import:R1206")
      (libsource (lib "eagle-import") (part "resistor_R-US_R1206"))
    )
    (comp (ref "R4")
      (value "470")
      (footprint "eagle-import:R1206")
      (libsource (lib "eagle-import") (part "resistor_R-US_R1206"))
    )
    (comp (ref "R5")
      (value "470")
      (footprint "eagle-import:R1206")
      (libsource (lib "eagle-import") (part "resistor_R-US_R1206"))
    )
    (comp (ref "R6")
      (value "470")
      (footprint "eagle-import:R1206")
      (libsource (lib "eagle-import") (part "resistor_R-US_R1206"))
    )
    (comp (ref "R7")
      (value "1K")
      (footprint "eagle-import:R1206")
      (libsource (lib "eagle-import") (part "resistor_R-US_R1206"))
    )
    (comp (ref "R8")
      (value "1K")
      (footprint "eagle-import:R1206")
      (libsource (lib "eagle-import") (part "resistor_R-US_R1206"))
    )
    (comp (ref "R9")
      (value "1K")
      (footprint "eagle-import:R1206")
      (libsource (lib "eagle-import") (part "resistor_R-US_R1206"))
    )
    (comp (ref "R10")
      (value "4.7K")
      (footprint "eagle-import:R1206")
      (libsource (lib "eagle-import") (part "resistor_R-US_R1206"))
    )
    (comp (ref "R11")
      (value "4.7K")
      (footprint "eagle-import:R1206")
      (libsource (lib "eagle-import") (part "resistor_R-US_R1206"))
    )
    (comp (ref "R12")
      (value "4.7K")
      (footprint "eagle-import:R1206")
      (libsource (lib "eagle-import") (part "resistor_R-US_R1206"))
    )
    (comp (ref "R13")
      (value "10K")
      (footprint "eagle-import:R1206")
      (libsource (lib "eagle-import") (part "resistor_R-US_R1206"))
    )
    (comp (ref "R14")
      (value "10K")
      (footprint "eagle-import:R1206")
      (libsource (lib "eagle-import") (part "resistor_R-US_R1206"))
    )
    (comp (ref "R15")
      (value "10K")
      (footprint "eagle-import:R1206")
      (libsource (lib "eagle-import") (part "resistor_R-US_R1206"))
    )
    (comp (ref "R16")
      (value "10K")
      (footprint "eagle-import:R1206")
      (libsource (lib "eagle-import") (part "resistor_R-US_R1206"))
    )
    (comp (ref "R17")
      (value "10K")
      (footprint "eagle-import:R1206")
      (libsource (lib "eagle-import") (part "resistor_R-US_R1206"))
    )
    (comp (ref "R18")
      (value "10K")
      (footprint "eagle-import:R1206")
      (libsource (lib "eagle-import") (part "resistor_R-US_R1206"))
    )
    (comp (ref "R19")
      (value "15K")
      (footprint "eagle-import:R1206")
      (libsource (lib "eagle-import") (part "resistor_R-US_R1206"))
    )
    (comp (ref "R20")
      (value "15K")
      (footprint "eagle-import:R1206")
      (libsource (lib "eagle-import") (part "resistor_R-US_R1206"))
    )
    (comp (ref "R21")
      (value "15K")
      (footprint "eagle-import:R1206")
      (libsource (lib "eagle-import") (part "resistor_R-US_R1206"))
    )
    (comp (ref "R22")
      (value "47K")
      (footprint "eagle-import:R1206")
      (libsource (lib "eagle-import") (part "resistor_R-US_R1206"))
    )
    (comp (ref "R23")
      (value "47K")
      (footprint "eagle-import:R1206")
      (libsource (lib "eagle-import") (part "resistor_R-US_R1206"))
    )
    (comp (ref "R24")
      (value "47K")
      (footprint "eagle-import:R1206")
      (libsource (lib "eagle-import") (part "resistor_R-US_R1206"))
    )
    (comp (ref "R25")
      (value "100K")
      (footprint "eagle-import:R1206")
      (libsource (lib "eagle-import") (part "resistor_R-US_R1206"))
    )
    (comp (ref "R26")
      (value "100K")
      (footprint "eagle-import:R1206")
      (libsource (lib "eagle-import") (part "resistor_R-US_R1206"))
    )
    (comp (ref "R27")
      (value "100K")
      (footprint "eagle-import:R1206")
      (libsource (lib "eagle-import") (part "resistor_R-US_R1206"))
    )
    (comp (ref "R28")
      (value "470K")
      (footprint "eagle-import:R1206")
      (libsource (lib "eagle-import") (part "resistor_R-US_R1206"))
    )
    (comp (ref "R29")
      (value "470K")
      (footprint "eagle-import:R1206")
      (libsource (lib "eagle-import") (part "resistor_R-US_R1206"))
    )
    (comp (ref "R30")
      (value "470K")
      (footprint "eagle-import:R1206")
      (libsource (lib "eagle-import") (part "resistor_R-US_R1206"))
    )
    (comp (ref "R31")
      (value "470")
      (footprint "eagle-import:R1206")
      (libsource (lib "eagle-import") (part "resistor_R-US_R1206"))
    )
    (comp (ref "R32")
      (value "330")
      (footprint "eagle-import:R1206")
      (libsource (lib "eagle-import") (part "resistor_R-US_R1206"))
    )
    (comp (ref "R33")
      (value "330")
      (footprint "eagle-import:R1206")
      (libsource (lib "eagle-import") (part "resistor_R-US_R1206"))
    )
    (comp (ref "R34")
      (value "330")
      (footprint "eagle-import:R1206")
      (libsource (lib "eagle-import") (part "resistor_R-US_R1206"))
    )
    (comp (ref "R35")
      (value "330")
      (footprint "eagle-import:R1206")
      (libsource (lib "eagle-import") (part "resistor_R-US_R1206"))
    )
    (comp (ref "R36")
      (value "330")
      (footprint "eagle-import:R1206")
      (libsource (lib "eagle-import") (part "resistor_R-US_R1206"))
    )
    (comp (ref "R37")
      (value "330")
      (footprint "eagle-import:R1206")
      (libsource (lib "eagle-import") (part "resistor_R-US_R1206"))
    )
    (comp (ref "R38")
      (value "330")
      (footprint "eagle-import:R1206")
      (libsource (lib "eagle-import") (part "resistor_R-US_R1206"))
    )
    (comp (ref "S1")
      (value "DPDT_JS202011CQN")
      (footprint "eagle-import:DPDT_JS202011CQN")
      (libsource (lib "eagle-import") (part "DPDT_JS202011CQN"))
    )
    (comp (ref "U1")
      (value "USB")
      (footprint "eagle-import:FCI-10103594-0001LF")
      (libsource (lib "eagle-import") (part "USB-RECEPTABLE"))
    )
  )
  (nets
    (net (code "1") (name "3.3V") (class "Default")
      (node (ref "C32") (pin "1") (pinfunction "1_1") (pintype "passive"))
      (node (ref "C33") (pin "1") (pinfunction "1_1") (pintype "passive"))
      (node (ref "IC13") (pin "14") (pinfunction "VS_14") (pintype "bidirectional"))
      (node (ref "IC13") (pin "15") (pinfunction "VS_15") (pintype "bidirectional"))
      (node (ref "IC14") (pin "5") (pinfunction "OUT_5") (pintype "passive"))
    )
    (net (code "2") (name "A1A") (class "Default")
      (node (ref "AR1") (pin "9") (pinfunction "9_9") (pintype "bidirectional"))
      (node (ref "IC3") (pin "1") (pinfunction "1A_1") (pintype "input"))
      (node (ref "PH45") (pin "1") (pinfunction "1_1") (pintype "passive"))
    )
    (net (code "3") (name "A1B") (class "Default")
      (node (ref "AR1") (pin "8") (pinfunction "8_8") (pintype "bidirectional"))
      (node (ref "IC3") (pin "2") (pinfunction "1B_2") (pintype "input"))
      (node (ref "PH45") (pin "2") (pinfunction "2_2") (pintype "passive"))
    )
    (net (code "4") (name "A1Y") (class "Default")
      (node (ref "IC3") (pin "3") (pinfunction "1Y_3") (pintype "output"))
      (node (ref "PH36") (pin "1") (pinfunction "1_1") (pintype "passive"))
    )
    (net (code "5") (name "A2A") (class "Default")
      (node (ref "AR1") (pin "7") (pinfunction "7_7") (pintype "bidirectional"))
      (node (ref "IC3") (pin "4") (pinfunction "2A_4") (pintype "input"))
      (node (ref "PH45") (pin "3") (pinfunction "3_3") (pintype "passive"))
    )
    (net (code "6") (name "A2B") (class "Default")
      (node (ref "AR1") (pin "6") (pinfunction "6_6") (pintype "bidirectional"))
      (node (ref "IC3") (pin "5") (pinfunction "2B_5") (pintype "input"))
      (node (ref "PH45") (pin "4") (pinfunction "4_4") (pintype "passive"))
    )
    (net (code "7") (name "A2Y") (class "Default")
      (node (ref "IC3") (pin "6") (pinfunction "2Y_6") (pintype "output"))
      (node (ref "PH36") (pin "2") (pinfunction "2_2") (pintype "passive"))
    )
    (net (code "8") (name "A3A") (class "Default")
      (node (ref "AR1") (pin "1") (pinfunction "1_1") (pintype "bidirectional"))
      (node (ref "IC3") (pin "9") (pinfunction "3A_9") (pintype "input"))
      (node (ref "PH45") (pin "5") (pinfunction "5_5") (pintype "passive"))
    )
    (net (code "9") (name "A3B") (class "Default")
      (node (ref "AR1") (pin "2") (pinfunction "2_2") (pintype "bidirectional"))
      (node (ref "IC3") (pin "10") (pinfunction "3B_10") (pintype "input"))
      (node (ref "PH45") (pin "6") (pinfunction "6_6") (pintype "passive"))
    )
    (net (code "10") (name "A3Y") (class "Default")
      (node (ref "IC3") (pin "8") (pinfunction "3Y_8") (pintype "output"))
      (node (ref "PH36") (pin "3") (pinfunction "3_3") (pintype "passive"))
    )
    (net (code "11") (name "A4A") (class "Default")
      (node (ref "AR1") (pin "3") (pinfunction "3_3") (pintype "bidirectional"))
      (node (ref "IC3") (pin "12") (pinfunction "4A_12") (pintype "input"))
      (node (ref "PH45") (pin "7") (pinfunction "7_7") (pintype "passive"))
    )
    (net (code "12") (name "A4B") (class "Default")
      (node (ref "AR1") (pin "4") (pinfunction "4_4") (pintype "bidirectional"))
      (node (ref "IC3") (pin "13") (pinfunction "4B_13") (pintype "input"))
      (node (ref "PH45") (pin "8") (pinfunction "8_8") (pintype "passive"))
    )
    (net (code "13") (name "A4Y") (class "Default")
      (node (ref "IC3") (pin "11") (pinfunction "4Y_11") (pintype "output"))
      (node (ref "PH36") (pin "4") (pinfunction "4_4") (pintype "passive"))
    )
    (net (code "14") (name "B") (class "Default")
      (node (ref "PH11") (pin "3") (pinfunction "3_3") (pintype "passive"))
      (node (ref "R59") (pin "2") (pinfunction "2_2") (pintype "passive"))
    )
    (net (code "15") (name "D0") (class "Default")
      (node (ref "PH41") (pin "1") (pinfunction "1_1") (pintype "passive"))
      (node (ref "PH63") (pin "1") (pinfunction "1_1") (pintype "passive"))
      (node (ref "R32") (pin "2") (pinfunction "2_2") (pintype "passive"))
    )
    (net (code "16") (name "D1") (class "Default")
      (node (ref "PH41") (pin "2") (pinfunction "2_2") (pintype "passive"))
      (node (ref "PH63") (pin "2") (pinfunction "2_2") (pintype "passive"))
    )
    (net (code "17") (name "D2") (class "Default")
      (node (ref "PH41") (pin "3") (pinfunction "3_3") (pintype "passive"))
      (node (ref "PH63") (pin "3") (pinfunction "3_3") (pintype "passive"))
      (node (ref "R33") (pin "2") (pinfunction "2_2") (pintype "passive"))
    )
    (net (code "18") (name "D3") (class "Default")
      (node (ref "PH41") (pin "4") (pinfunction "4_4") (pintype "passive"))
      (node (ref "PH63") (pin "4") (pinfunction "4_4") (pintype "passive"))
    )
    (net (code "19") (name "D4") (class "Default")
      (node (ref "PH41") (pin "5") (pinfunction "5_5") (pintype "passive"))
      (node (ref "PH63") (pin "5") (pinfunction "5_5") (pintype "passive"))
      (node (ref "R34") (pin "2") (pinfunction "2_2") (pintype "passive"))
    )
    (net (code "20") (name "D5") (class "Default")
      (node (ref "PH41") (pin "6") (pinfunction "6_6") (pintype "passive"))
      (node (ref "PH63") (pin "6") (pinfunction "6_6") (pintype "passive"))
    )
    (net (code "21") (name "D6") (class "Default")
      (node (ref "PH41") (pin "7") (pinfunction "7_7") (pintype "passive"))
      (node (ref "PH63") (pin "7") (pinfunction "7_7") (pintype "passive"))
      (node (ref "R35") (pin "2") (pinfunction "2_2") (pintype "passive"))
    )
    (net (code "22") (name "D7") (class "Default")
      (node (ref "PH41") (pin "8") (pinfunction "8_8") (pintype "passive"))
      (node (ref "PH63") (pin "8") (pinfunction "8_8") (pintype "passive"))
    )
    (net (code "23") (name "D8") (class "Default")
      (node (ref "PH41") (pin "9") (pinfunction "9_9") (pintype "passive"))
      (node (ref "PH63") (pin "9") (pinfunction "9_9") (pintype "passive"))
      (node (ref "R36") (pin "2") (pinfunction "2_2") (pintype "passive"))
    )
    (net (code "24") (name "D9") (class "Default")
      (node (ref "PH41") (pin "10") (pinfunction "10_10") (pintype "passive"))
      (node (ref "PH63") (pin "10") (pinfunction "10_10") (pintype "passive"))
    )
    (net (code "25") (name "D10") (class "Default")
      (node (ref "PH41") (pin "11") (pinfunction "11_11") (pintype "passive"))
      (node (ref "PH63") (pin "11") (pinfunction "11_11") (pintype "passive"))
      (node (ref "R37") (pin "2") (pinfunction "2_2") (pintype "passive"))
    )
    (net (code "26") (name "D11") (class "Default")
      (node (ref "PH41") (pin "12") (pinfunction "12_12") (pintype "passive"))
      (node (ref "PH63") (pin "12") (pinfunction "12_12") (pintype "passive"))
    )
    (net (code "27") (name "D12") (class "Default")
      (node (ref "PH41") (pin "13") (pinfunction "13_13") (pintype "passive"))
      (node (ref "PH63") (pin "13") (pinfunction "13_13") (pintype "passive"))
      (node (ref "R38") (pin "2") (pinfunction "2_2") (pintype "passive"))
    )
    (net (code "28") (name "D13") (class "Default")
      (node (ref "PH41") (pin "14") (pinfunction "14_14") (pintype "passive"))
      (node (ref "PH63") (pin "14") (pinfunction "14_14") (pintype "passive"))
    )
    (net (code "29") (name "DG1") (class "Default")
      (node (ref "DP1") (pin "9") (pinfunction "9_9") (pintype "bidirectional"))
      (node (ref "PH3") (pin "1") (pinfunction "1_1") (pintype "passive"))
    )
    (net (code "30") (name "DG2") (class "Default")
      (node (ref "DP1") (pin "4") (pinfunction "4_4") (pintype "bidirectional"))
      (node (ref "PH3") (pin "2") (pinfunction "2_2") (pintype "passive"))
    )
    (net (code "31") (name "DP") (class "Default")
      (node (ref "DP1") (pin "2") (pinfunction "2_2") (pintype "bidirectional"))
    )
    (net (code "32") (name "G") (class "Default")
      (node (ref "PH11") (pin "2") (pinfunction "2_2") (pintype "passive"))
      (node (ref "R57") (pin "2") (pinfunction "2_2") (pintype "passive"))
    )
    (net (code "33") (name "GND") (class "Default")
      (node (ref "AR1") (pin "10") (pinfunction "10_10") (pintype "bidirectional"))
      (node (ref "AR1") (pin "5") (pinfunction "5_5") (pintype "bidirectional"))
      (node (ref "AR2") (pin "10") (pinfunction "10_10") (pintype "bidirectional"))
      (node (ref "AR2") (pin "5") (pinfunction "5_5") (pintype "bidirectional"))
      (node (ref "AR3") (pin "10") (pinfunction "10_10") (pintype "bidirectional"))
      (node (ref "AR3") (pin "5") (pinfunction "5_5") (pintype "bidirectional"))
      (node (ref "AR4") (pin "10") (pinfunction "10_10") (pintype "bidirectional"))
      (node (ref "AR4") (pin "5") (pinfunction "5_5") (pintype "bidirectional"))
      (node (ref "C21") (pin "2") (pinfunction "2_2") (pintype "passive"))
      (node (ref "C23") (pin "2") (pinfunction "2_2") (pintype "passive"))
      (node (ref "C24") (pin "2") (pinfunction "2_2") (pintype "passive"))
      (node (ref "C25") (pin "2") (pinfunction "2_2") (pintype "passive"))
      (node (ref "C27") (pin "-") (pinfunction "-_-") (pintype "passive"))
      (node (ref "C29") (pin "2") (pinfunction "2_2") (pintype "passive"))
      (node (ref "C30") (pin "2") (pinfunction "2_2") (pintype "passive"))
      (node (ref "C31") (pin "2") (pinfunction "2_2") (pintype "passive"))
      (node (ref "C32") (pin "2") (pinfunction "2_2") (pintype "passive"))
      (node (ref "C33") (pin "2") (pinfunction "2_2") (pintype "passive"))
      (node (ref "C34") (pin "2") (pinfunction "2_2") (pintype "passive"))
      (node (ref "H1") (pin "B2,8") (pinfunction "MOUNT_B2,8") (pintype "passive"))
      (node (ref "H2") (pin "B2,8") (pinfunction "MOUNT_B2,8") (pintype "passive"))
      (node (ref "H3") (pin "B2,8") (pinfunction "MOUNT_B2,8") (pintype "passive"))
      (node (ref "H4") (pin "B2,8") (pinfunction "MOUNT_B2,8") (pintype "passive"))
      (node (ref "IC1") (pin "11") (pinfunction "GND_11") (pintype "passive"))
      (node (ref "IC10") (pin "GND") (pinfunction "GND_GND") (pintype "bidirectional"))
      (node (ref "IC10") (pin "RBI") (pinfunction "RBI_RBI") (pintype "bidirectional"))
      (node (ref "IC11") (pin "11") (pinfunction "GND_11") (pintype "output"))
      (node (ref "IC11") (pin "15") (pinfunction "PGND1_15") (pintype "output"))
      (node (ref "IC11") (pin "2") (pinfunction "PGND_2") (pintype "input"))
      (node (ref "IC11") (pin "9") (pinfunction "NC_9") (pintype "output"))
      (node (ref "IC13") (pin "6") (pinfunction "GND_6") (pintype "bidirectional"))
      (node (ref "IC13") (pin "7") (pinfunction "GND_7") (pintype "bidirectional"))
      (node (ref "IC14") (pin "2") (pinfunction "GND_2") (pintype "input"))
      (node (ref "IC2") (pin "11") (pinfunction "GND_11") (pintype "passive"))
      (node (ref "IC3") (pin "7") (pinfunction "GND_7") (pintype "passive"))
      (node (ref "IC4") (pin "7") (pinfunction "GND_7") (pintype "passive"))
      (node (ref "IC5") (pin "7") (pinfunction "GND_7") (pintype "passive"))
      (node (ref "IC6") (pin "12") (pinfunction "R_12") (pintype "input"))
      (node (ref "IC6") (pin "4") (pinfunction "R_4") (pintype "input"))
      (node (ref "IC6") (pin "7") (pinfunction "S_7") (pintype "input"))
      (node (ref "IC6") (pin "8") (pinfunction "VSS_8") (pintype "power_in"))
      (node (ref "IC6") (pin "9") (pinfunction "S_9") (pintype "input"))
      (node (ref "IC7") (pin "12") (pinfunction "R_12") (pintype "input"))
      (node (ref "IC7") (pin "4") (pinfunction "R_4") (pintype "input"))
      (node (ref "IC7") (pin "7") (pinfunction "S_7") (pintype "input"))
      (node (ref "IC7") (pin "8") (pinfunction "VSS_8") (pintype "power_in"))
      (node (ref "IC7") (pin "9") (pinfunction "S_9") (pintype "input"))
      (node (ref "IC8") (pin "1") (pinfunction "GND_1") (pintype "power_in"))
      (node (ref "L0") (pin "C") (pinfunction "C_C") (pintype "passive"))
      (node (ref "L1") (pin "C") (pinfunction "C_C") (pintype "passive"))
      (node (ref "L10") (pin "C") (pinfunction "C_C") (pintype "passive"))
      (node (ref "L11") (pin "C") (pinfunction "C_C") (pintype "passive"))
      (node (ref "L12") (pin "C") (pinfunction "C_C") (pintype "passive"))
      (node (ref "L13") (pin "C") (pinfunction "C_C") (pintype "passive"))
      (node (ref "L14") (pin "C") (pinfunction "C_C") (pintype "passive"))
      (node (ref "L15") (pin "C") (pinfunction "C_C") (pintype "passive"))
      (node (ref "L16") (pin "C") (pinfunction "C_C") (pintype "passive"))
      (node (ref "L17") (pin "C") (pinfunction "C_C") (pintype "passive"))
      (node (ref "L2") (pin "C") (pinfunction "C_C") (pintype "passive"))
      (node (ref "L3") (pin "C") (pinfunction "C_C") (pintype "passive"))
      (node (ref "L4") (pin "C") (pinfunction "C_C") (pintype "passive"))
      (node (ref "L5") (pin "C") (pinfunction "C_C") (pintype "passive"))
      (node (ref "L6") (pin "C") (pinfunction "C_C") (pintype "passive"))
      (node (ref "L7") (pin "C") (pinfunction "C_C") (pintype "passive"))
      (node (ref "L8") (pin "C") (pinfunction "C_C") (pintype "passive"))
      (node (ref "L9") (pin "C") (pinfunction "C_C") (pintype "passive"))
      (node (ref "LED_") (pin "4") (pinfunction "C_4") (pintype "passive"))
      (node (ref "LED_") (pin "5") (pinfunction "C_5") (pintype "passive"))
      (node (ref "LED_") (pin "6") (pinfunction "C_6") (pintype "passive"))
      (node (ref "PH38") (pin "1") (pinfunction "1_1") (pintype "passive"))
      (node (ref "PH62") (pin "1") (pinfunction "1_1") (pintype "passive"))
      (node (ref "PH62") (pin "10") (pinfunction "10_10") (pintype "passive"))
      (node (ref "PH62") (pin "11") (pinfunction "11_11") (pintype "passive"))
      (node (ref "PH62") (pin "12") (pinfunction "12_12") (pintype "passive"))
      (node (ref "PH62") (pin "13") (pinfunction "13_13") (pintype "passive"))
      (node (ref "PH62") (pin "14") (pinfunction "14_14") (pintype "passive"))
      (node (ref "PH62") (pin "15") (pinfunction "15_15") (pintype "passive"))
      (node (ref "PH62") (pin "16") (pinfunction "16_16") (pintype "passive"))
      (node (ref "PH62") (pin "17") (pinfunction "17_17") (pintype "passive"))
      (node (ref "PH62") (pin "18") (pinfunction "18_18") (pintype "passive"))
      (node (ref "PH62") (pin "19") (pinfunction "19_19") (pintype "passive"))
      (node (ref "PH62") (pin "2") (pinfunction "2_2") (pintype "passive"))
      (node (ref "PH62") (pin "20") (pinfunction "20_20") (pintype "passive"))
      (node (ref "PH62") (pin "21") (pinfunction "21_21") (pintype "passive"))
      (node (ref "PH62") (pin "22") (pinfunction "22_22") (pintype "passive"))
      (node (ref "PH62") (pin "23") (pinfunction "23_23") (pintype "passive"))
      (node (ref "PH62") (pin "24") (pinfunction "24_24") (pintype "passive"))
      (node (ref "PH62") (pin "25") (pinfunction "25_25") (pintype "passive"))
      (node (ref "PH62") (pin "26") (pinfunction "26_26") (pintype "passive"))
      (node (ref "PH62") (pin "27") (pinfunction "27_27") (pintype "passive"))
      (node (ref "PH62") (pin "28") (pinfunction "28_28") (pintype "passive"))
      (node (ref "PH62") (pin "29") (pinfunction "29_29") (pintype "passive"))
      (node (ref "PH62") (pin "3") (pinfunction "3_3") (pintype "passive"))
      (node (ref "PH62") (pin "30") (pinfunction "30_30") (pintype "passive"))
      (node (ref "PH62") (pin "4") (pinfunction "4_4") (pintype "passive"))
      (node (ref "PH62") (pin "5") (pinfunction "5_5") (pintype "passive"))
      (node (ref "PH62") (pin "6") (pinfunction "6_6") (pintype "passive"))
      (node (ref "PH62") (pin "7") (pinfunction "7_7") (pintype "passive"))
      (node (ref "PH62") (pin "8") (pinfunction "8_8") (pintype "passive"))
      (node (ref "PH62") (pin "9") (pinfunction "9_9") (pintype "passive"))
      (node (ref "PH63") (pin "16") (pinfunction "16_16") (pintype "passive"))
      (node (ref "R67") (pin "1") (pinfunction "1_1") (pintype "passive"))
      (node (ref "U1") (pin "5") (pinfunction "GND_5") (pintype "bidirectional"))
      (node (ref "U2") (pin "HB") (pinfunction "H2_HB") (pintype "bidirectional"))
    )
    (net (code "34") (name "I1A") (class "Default")
      (node (ref "AR3") (pin "9") (pinfunction "9_9") (pintype "bidirectional"))
      (node (ref "IC5") (pin "1") (pinfunction "1A_1") (pintype "input"))
      (node (ref "PH39") (pin "1") (pinfunction "1_1") (pintype "passive"))
    )
    (net (code "35") (name "I1Y") (class "Default")
      (node (ref "IC5") (pin "2") (pinfunction "1Y_2") (pintype "output"))
      (node (ref "PH40") (pin "1") (pinfunction "1_1") (pintype "passive"))
    )
    (net (code "36") (name "I2A") (class "Default")
      (node (ref "AR3") (pin "3") (pinfunction "3_3") (pintype "bidirectional"))
      (node (ref "IC5") (pin "3") (pinfunction "2A_3") (pintype "input"))
      (node (ref "PH39") (pin "2") (pinfunction "2_2") (pintype "passive"))
    )
    (net (code "37") (name "I2Y") (class "Default")
      (node (ref "IC5") (pin "4") (pinfunction "2Y_4") (pintype "output"))
      (node (ref "PH40") (pin "2") (pinfunction "2_2") (pintype "passive"))
    )
    (net (code "38") (name "I3A") (class "Default")
      (node (ref "AR3") (pin "7") (pinfunction "7_7") (pintype "bidirectional"))
      (node (ref "IC5") (pin "5") (pinfunction "3A_5") (pintype "input"))
      (node (ref "PH39") (pin "3") (pinfunction "3_3") (pintype "passive"))
    )
    (net (code "39") (name "I3Y") (class "Default")
      (node (ref "IC5") (pin "6") (pinfunction "3Y_6") (pintype "output"))
      (node (ref "PH40") (pin "3") (pinfunction "3_3") (pintype "passive"))
    )
    (net (code "40") (name "I4A") (class "Default")
      (node (ref "AR3") (pin "6") (pinfunction "6_6") (pintype "bidirectional"))
      (node (ref "IC5") (pin "9") (pinfunction "4A_9") (pintype "input"))
      (node (ref "PH39") (pin "4") (pinfunction "4_4") (pintype "passive"))
    )
    (net (code "41") (name "I4Y") (class "Default")
      (node (ref "IC5") (pin "8") (pinfunction "4Y_8") (pintype "output"))
      (node (ref "PH40") (pin "4") (pinfunction "4_4") (pintype "passive"))
    )
    (net (code "42") (name "I5A") (class "Default")
      (node (ref "AR3") (pin "1") (pinfunction "1_1") (pintype "bidirectional"))
      (node (ref "IC5") (pin "11") (pinfunction "5A_11") (pintype "input"))
      (node (ref "PH39") (pin "5") (pinfunction "5_5") (pintype "passive"))
    )
    (net (code "43") (name "I5Y") (class "Default")
      (node (ref "IC5") (pin "10") (pinfunction "5Y_10") (pintype "output"))
      (node (ref "PH40") (pin "5") (pinfunction "5_5") (pintype "passive"))
    )
    (net (code "44") (name "I6A") (class "Default")
      (node (ref "AR3") (pin "2") (pinfunction "2_2") (pintype "bidirectional"))
      (node (ref "IC5") (pin "13") (pinfunction "6A_13") (pintype "input"))
      (node (ref "PH39") (pin "6") (pinfunction "6_6") (pintype "passive"))
    )
    (net (code "45") (name "I6Y") (class "Default")
      (node (ref "IC5") (pin "12") (pinfunction "6Y_12") (pintype "output"))
      (node (ref "PH40") (pin "6") (pinfunction "6_6") (pintype "passive"))
    )
    (net (code "46") (name "IA") (class "Default")
      (node (ref "AR4") (pin "9") (pinfunction "9_9") (pintype "bidirectional"))
      (node (ref "IC10") (pin "IA") (pinfunction "IA_IA") (pintype "bidirectional"))
      (node (ref "PH35") (pin "1") (pinfunction "1_1") (pintype "passive"))
    )
    (net (code "47") (name "IB") (class "Default")
      (node (ref "AR4") (pin "8") (pinfunction "8_8") (pintype "bidirectional"))
      (node (ref "IC10") (pin "IB") (pinfunction "IB_IB") (pintype "bidirectional"))
      (node (ref "PH35") (pin "2") (pinfunction "2_2") (pintype "passive"))
    )
    (net (code "48") (name "IC") (class "Default")
      (node (ref "AR4") (pin "7") (pinfunction "7_7") (pintype "bidirectional"))
      (node (ref "IC10") (pin "IC") (pinfunction "IC_IC") (pintype "bidirectional"))
      (node (ref "PH35") (pin "3") (pinfunction "3_3") (pintype "passive"))
    )
    (net (code "49") (name "ID") (class "Default")
      (node (ref "AR4") (pin "6") (pinfunction "6_6") (pintype "bidirectional"))
      (node (ref "IC10") (pin "ID") (pinfunction "ID_ID") (pintype "bidirectional"))
      (node (ref "PH35") (pin "4") (pinfunction "4_4") (pintype "passive"))
    )
    (net (code "50") (name "INL") (class "Default")
      (node (ref "IC11") (pin "7") (pinfunction "INL_7") (pintype "input"))
      (node (ref "R60") (pin "1") (pinfunction "1_1") (pintype "passive"))
    )
    (net (code "51") (name "INR") (class "Default")
      (node (ref "IC11") (pin "10") (pinfunction "INR_10") (pintype "output"))
      (node (ref "R40") (pin "1") (pinfunction "1_1") (pintype "passive"))
    )
    (net (code "52") (name "IN_L") (class "Default")
      (node (ref "C26") (pin "1") (pinfunction "1_1") (pintype "passive"))
      (node (ref "PH38") (pin "3") (pinfunction "3_3") (pintype "passive"))
    )
    (net (code "53") (name "IN_R") (class "Default")
      (node (ref "C22") (pin "1") (pinfunction "1_1") (pintype "passive"))
      (node (ref "PH38") (pin "2") (pinfunction "2_2") (pintype "passive"))
    )
    (net (code "54") (name "L1") (class "Default")
      (node (ref "PH47") (pin "9") (pinfunction "9_9") (pintype "passive"))
      (node (ref "R48") (pin "2") (pinfunction "2_2") (pintype "passive"))
    )
    (net (code "55") (name "L2") (class "Default")
      (node (ref "PH47") (pin "8") (pinfunction "8_8") (pintype "passive"))
      (node (ref "R49") (pin "2") (pinfunction "2_2") (pintype "passive"))
    )
    (net (code "56") (name "L3") (class "Default")
      (node (ref "PH47") (pin "7") (pinfunction "7_7") (pintype "passive"))
      (node (ref "R50") (pin "2") (pinfunction "2_2") (pintype "passive"))
    )
    (net (code "57") (name "L4") (class "Default")
      (node (ref "PH47") (pin "6") (pinfunction "6_6") (pintype "passive"))
      (node (ref "R51") (pin "2") (pinfunction "2_2") (pintype "passive"))
    )
    (net (code "58") (name "L5") (class "Default")
      (node (ref "PH47") (pin "5") (pinfunction "5_5") (pintype "passive"))
      (node (ref "R52") (pin "2") (pinfunction "2_2") (pintype "passive"))
    )
    (net (code "59") (name "L6") (class "Default")
      (node (ref "PH47") (pin "4") (pinfunction "4_4") (pintype "passive"))
      (node (ref "R53") (pin "2") (pinfunction "2_2") (pintype "passive"))
    )
    (net (code "60") (name "L7") (class "Default")
      (node (ref "PH47") (pin "3") (pinfunction "3_3") (pintype "passive"))
      (node (ref "R54") (pin "2") (pinfunction "2_2") (pintype "passive"))
    )
    (net (code "61") (name "L8") (class "Default")
      (node (ref "PH47") (pin "2") (pinfunction "2_2") (pintype "passive"))
      (node (ref "R55") (pin "2") (pinfunction "2_2") (pintype "passive"))
    )
    (net (code "62") (name "L9") (class "Default")
      (node (ref "PH47") (pin "1") (pinfunction "1_1") (pintype "passive"))
      (node (ref "R56") (pin "2") (pinfunction "2_2") (pintype "passive"))
    )
    (net (code "63") (name "MUTE") (class "Default")
      (node (ref "IC11") (pin "5") (pinfunction "MUTE_5") (pintype "input"))
    )
    (net (code "64") (name "Net-(C1-Pad1)") (class "Default")
      (node (ref "C1") (pin "1") (pinfunction "1_1") (pintype "passive"))
      (node (ref "PH56") (pin "10") (pinfunction "10_10") (pintype "passive"))
    )
    (net (code "65") (name "Net-(C1-Pad2)") (class "Default")
      (node (ref "C1") (pin "2") (pinfunction "2_2") (pintype "passive"))
      (node (ref "PH57") (pin "1") (pinfunction "1_1") (pintype "passive"))
    )
    (net (code "66") (name "Net-(C2-Pad1)") (class "Default")
      (node (ref "C2") (pin "1") (pinfunction "1_1") (pintype "passive"))
      (node (ref "PH54") (pin "10") (pinfunction "10_10") (pintype "passive"))
    )
    (net (code "67") (name "Net-(C2-Pad2)") (class "Default")
      (node (ref "C2") (pin "2") (pinfunction "2_2") (pintype "passive"))
      (node (ref "PH55") (pin "1") (pinfunction "1_1") (pintype "passive"))
    )
    (net (code "68") (name "Net-(C3-Pad1)") (class "Default")
      (node (ref "C3") (pin "1") (pinfunction "1_1") (pintype "passive"))
      (node (ref "PH56") (pin "9") (pinfunction "9_9") (pintype "passive"))
    )
    (net (code "69") (name "Net-(C3-Pad2)") (class "Default")
      (node (ref "C3") (pin "2") (pinfunction "2_2") (pintype "passive"))
      (node (ref "PH57") (pin "2") (pinfunction "2_2") (pintype "passive"))
    )
    (net (code "70") (name "Net-(C4-Pad1)") (class "Default")
      (node (ref "C4") (pin "1") (pinfunction "1_1") (pintype "passive"))
      (node (ref "PH54") (pin "9") (pinfunction "9_9") (pintype "passive"))
    )
    (net (code "71") (name "Net-(C4-Pad2)") (class "Default")
      (node (ref "C4") (pin "2") (pinfunction "2_2") (pintype "passive"))
      (node (ref "PH55") (pin "2") (pinfunction "2_2") (pintype "passive"))
    )
    (net (code "72") (name "Net-(C5-Pad1)") (class "Default")
      (node (ref "C5") (pin "1") (pinfunction "1_1") (pintype "passive"))
      (node (ref "PH56") (pin "8") (pinfunction "8_8") (pintype "passive"))
    )
    (net (code "73") (name "Net-(C5-Pad2)") (class "Default")
      (node (ref "C5") (pin "2") (pinfunction "2_2") (pintype "passive"))
      (node (ref "PH57") (pin "3") (pinfunction "3_3") (pintype "passive"))
    )
    (net (code "74") (name "Net-(C6-Pad1)") (class "Default")
      (node (ref "C6") (pin "1") (pinfunction "1_1") (pintype "passive"))
      (node (ref "PH54") (pin "8") (pinfunction "8_8") (pintype "passive"))
    )
    (net (code "75") (name "Net-(C6-Pad2)") (class "Default")
      (node (ref "C6") (pin "2") (pinfunction "2_2") (pintype "passive"))
      (node (ref "PH55") (pin "3") (pinfunction "3_3") (pintype "passive"))
    )
    (net (code "76") (name "Net-(C7-Pad1)") (class "Default")
      (node (ref "C7") (pin "1") (pinfunction "1_1") (pintype "passive"))
      (node (ref "PH56") (pin "7") (pinfunction "7_7") (pintype "passive"))
    )
    (net (code "77") (name "Net-(C7-Pad2)") (class "Default")
      (node (ref "C7") (pin "2") (pinfunction "2_2") (pintype "passive"))
      (node (ref "PH57") (pin "4") (pinfunction "4_4") (pintype "passive"))
    )
    (net (code "78") (name "Net-(C8-Pad1)") (class "Default")
      (node (ref "C8") (pin "1") (pinfunction "1_1") (pintype "passive"))
      (node (ref "PH54") (pin "7") (pinfunction "7_7") (pintype "passive"))
    )
    (net (code "79") (name "Net-(C8-Pad2)") (class "Default")
      (node (ref "C8") (pin "2") (pinfunction "2_2") (pintype "passive"))
      (node (ref "PH55") (pin "4") (pinfunction "4_4") (pintype "passive"))
    )
    (net (code "80") (name "Net-(C9-Pad1)") (class "Default")
      (node (ref "C9") (pin "1") (pinfunction "1_1") (pintype "passive"))
      (node (ref "PH56") (pin "6") (pinfunction "6_6") (pintype "passive"))
    )
    (net (code "81") (name "Net-(C9-Pad2)") (class "Default")
      (node (ref "C9") (pin "2") (pinfunction "2_2") (pintype "passive"))
      (node (ref "PH57") (pin "5") (pinfunction "5_5") (pintype "passive"))
    )
    (net (code "82") (name "Net-(C10-Pad1)") (class "Default")
      (node (ref "C10") (pin "1") (pinfunction "1_1") (pintype "passive"))
      (node (ref "PH54") (pin "6") (pinfunction "6_6") (pintype "passive"))
    )
    (net (code "83") (name "Net-(C10-Pad2)") (class "Default")
      (node (ref "C10") (pin "2") (pinfunction "2_2") (pintype "passive"))
      (node (ref "PH55") (pin "5") (pinfunction "5_5") (pintype "passive"))
    )
    (net (code "84") (name "Net-(C11-Pad1)") (class "Default")
      (node (ref "C11") (pin "1") (pinfunction "1_1") (pintype "passive"))
      (node (ref "PH56") (pin "5") (pinfunction "5_5") (pintype "passive"))
    )
    (net (code "85") (name "Net-(C11-Pad2)") (class "Default")
      (node (ref "C11") (pin "2") (pinfunction "2_2") (pintype "passive"))
      (node (ref "PH57") (pin "6") (pinfunction "6_6") (pintype "passive"))
    )
    (net (code "86") (name "Net-(C12-Pad1)") (class "Default")
      (node (ref "C12") (pin "1") (pinfunction "1_1") (pintype "passive"))
      (node (ref "PH54") (pin "5") (pinfunction "5_5") (pintype "passive"))
    )
    (net (code "87") (name "Net-(C12-Pad2)") (class "Default")
      (node (ref "C12") (pin "2") (pinfunction "2_2") (pintype "passive"))
      (node (ref "PH55") (pin "6") (pinfunction "6_6") (pintype "passive"))
    )
    (net (code "88") (name "Net-(C13-Pad1)") (class "Default")
      (node (ref "C13") (pin "1") (pinfunction "1_1") (pintype "passive"))
      (node (ref "PH56") (pin "4") (pinfunction "4_4") (pintype "passive"))
    )
    (net (code "89") (name "Net-(C13-Pad2)") (class "Default")
      (node (ref "C13") (pin "2") (pinfunction "2_2") (pintype "passive"))
      (node (ref "PH57") (pin "7") (pinfunction "7_7") (pintype "passive"))
    )
    (net (code "90") (name "Net-(C14-Pad1)") (class "Default")
      (node (ref "C14") (pin "1") (pinfunction "1_1") (pintype "passive"))
      (node (ref "PH54") (pin "4") (pinfunction "4_4") (pintype "passive"))
    )
    (net (code "91") (name "Net-(C14-Pad2)") (class "Default")
      (node (ref "C14") (pin "2") (pinfunction "2_2") (pintype "passive"))
      (node (ref "PH55") (pin "7") (pinfunction "7_7") (pintype "passive"))
    )
    (net (code "92") (name "Net-(C15-Pad1)") (class "Default")
      (node (ref "C15") (pin "1") (pinfunction "1_1") (pintype "passive"))
      (node (ref "PH56") (pin "3") (pinfunction "3_3") (pintype "passive"))
    )
    (net (code "93") (name "Net-(C15-Pad2)") (class "Default")
      (node (ref "C15") (pin "2") (pinfunction "2_2") (pintype "passive"))
      (node (ref "PH57") (pin "8") (pinfunction "8_8") (pintype "passive"))
    )
    (net (code "94") (name "Net-(C16-Pad1)") (class "Default")
      (node (ref "C16") (pin "1") (pinfunction "1_1") (pintype "passive"))
      (node (ref "PH54") (pin "3") (pinfunction "3_3") (pintype "passive"))
    )
    (net (code "95") (name "Net-(C16-Pad2)") (class "Default")
      (node (ref "C16") (pin "2") (pinfunction "2_2") (pintype "passive"))
      (node (ref "PH55") (pin "8") (pinfunction "8_8") (pintype "passive"))
    )
    (net (code "96") (name "Net-(C17-Pad+)") (class "Default")
      (node (ref "C17") (pin "+") (pinfunction "+_+") (pintype "passive"))
      (node (ref "PH56") (pin "2") (pinfunction "2_2") (pintype "passive"))
    )
    (net (code "97") (name "Net-(C17-Pad-)") (class "Default")
      (node (ref "C17") (pin "-") (pinfunction "-_-") (pintype "passive"))
      (node (ref "PH57") (pin "9") (pinfunction "9_9") (pintype "passive"))
    )
    (net (code "98") (name "Net-(C18-Pad+)") (class "Default")
      (node (ref "C18") (pin "+") (pinfunction "+_+") (pintype "passive"))
      (node (ref "PH54") (pin "2") (pinfunction "2_2") (pintype "passive"))
    )
    (net (code "99") (name "Net-(C18-Pad-)") (class "Default")
      (node (ref "C18") (pin "-") (pinfunction "-_-") (pintype "passive"))
      (node (ref "PH55") (pin "9") (pinfunction "9_9") (pintype "passive"))
    )
    (net (code "100") (name "Net-(C19-Pad+)") (class "Default")
      (node (ref "C19") (pin "+") (pinfunction "+_+") (pintype "passive"))
      (node (ref "C35") (pin "+") (pinfunction "+_+") (pintype "passive"))
      (node (ref "PH56") (pin "1") (pinfunction "1_1") (pintype "passive"))
    )
    (net (code "101") (name "Net-(C19-Pad-)") (class "Default")
      (node (ref "C19") (pin "-") (pinfunction "-_-") (pintype "passive"))
      (node (ref "C35") (pin "-") (pinfunction "-_-") (pintype "passive"))
      (node (ref "PH57") (pin "10") (pinfunction "10_10") (pintype "passive"))
    )
    (net (code "102") (name "Net-(C20-Pad+)") (class "Default")
      (node (ref "C20") (pin "+") (pinfunction "+_+") (pintype "passive"))
      (node (ref "C36") (pin "+") (pinfunction "+_+") (pintype "passive"))
      (node (ref "PH54") (pin "1") (pinfunction "1_1") (pintype "passive"))
    )
    (net (code "103") (name "Net-(C20-Pad-)") (class "Default")
      (node (ref "C20") (pin "-") (pinfunction "-_-") (pintype "passive"))
      (node (ref "C36") (pin "-") (pinfunction "-_-") (pintype "passive"))
      (node (ref "PH55") (pin "10") (pinfunction "10_10") (pintype "passive"))
    )
    (net (code "104") (name "Net-(C22-Pad2)") (class "Default")
      (node (ref "C22") (pin "2") (pinfunction "2_2") (pintype "passive"))
      (node (ref "R40") (pin "2") (pinfunction "2_2") (pintype "passive"))
    )
    (net (code "105") (name "Net-(C26-Pad2)") (class "Default")
      (node (ref "C26") (pin "2") (pinfunction "2_2") (pintype "passive"))
      (node (ref "R60") (pin "2") (pinfunction "2_2") (pintype "passive"))
    )
    (net (code "106") (name "Net-(D1-Pad+)") (class "Default")
      (node (ref "D1") (pin "+") (pinfunction "+_+") (pintype "passive"))
      (node (ref "PH32") (pin "1") (pinfunction "1_1") (pintype "passive"))
    )
    (net (code "107") (name "Net-(D1-Pad-)") (class "Default")
      (node (ref "D1") (pin "-") (pinfunction "-_-") (pintype "passive"))
      (node (ref "PH33") (pin "1") (pinfunction "1_1") (pintype "passive"))
    )
    (net (code "108") (name "Net-(D2-Pad+)") (class "Default")
      (node (ref "D2") (pin "+") (pinfunction "+_+") (pintype "passive"))
      (node (ref "PH32") (pin "2") (pinfunction "2_2") (pintype "passive"))
    )
    (net (code "109") (name "Net-(D2-Pad-)") (class "Default")
      (node (ref "D2") (pin "-") (pinfunction "-_-") (pintype "passive"))
      (node (ref "PH33") (pin "2") (pinfunction "2_2") (pintype "passive"))
    )
    (net (code "110") (name "Net-(D3-Pad+)") (class "Default")
      (node (ref "D3") (pin "+") (pinfunction "+_+") (pintype "passive"))
      (node (ref "PH32") (pin "3") (pinfunction "3_3") (pintype "passive"))
    )
    (net (code "111") (name "Net-(D3-Pad-)") (class "Default")
      (node (ref "D3") (pin "-") (pinfunction "-_-") (pintype "passive"))
      (node (ref "PH33") (pin "3") (pinfunction "3_3") (pintype "passive"))
    )
    (net (code "112") (name "Net-(D4-Pad+)") (class "Default")
      (node (ref "D4") (pin "+") (pinfunction "+_+") (pintype "passive"))
      (node (ref "PH32") (pin "4") (pinfunction "4_4") (pintype "passive"))
    )
    (net (code "113") (name "Net-(D4-Pad-)") (class "Default")
      (node (ref "D4") (pin "-") (pinfunction "-_-") (pintype "passive"))
      (node (ref "PH33") (pin "4") (pinfunction "4_4") (pintype "passive"))
    )
    (net (code "114") (name "Net-(IC1-1IN+)") (class "Default")
      (node (ref "IC1") (pin "3") (pinfunction "1IN+_3") (pintype "input"))
      (node (ref "PH42") (pin "8") (pinfunction "8_8") (pintype "passive"))
    )
    (net (code "115") (name "Net-(IC1-1IN-)") (class "Default")
      (node (ref "IC1") (pin "2") (pinfunction "1IN-_2") (pintype "input"))
      (node (ref "PH42") (pin "7") (pinfunction "7_7") (pintype "passive"))
    )
    (net (code "116") (name "Net-(IC1-1OUT)") (class "Default")
      (node (ref "IC1") (pin "1") (pinfunction "1OUT_1") (pintype "output"))
      (node (ref "PH44") (pin "5") (pinfunction "5_5") (pintype "passive"))
    )
    (net (code "117") (name "Net-(IC1-2IN+)") (class "Default")
      (node (ref "IC1") (pin "5") (pinfunction "2IN+_5") (pintype "input"))
      (node (ref "PH42") (pin "6") (pinfunction "6_6") (pintype "passive"))
    )
    (net (code "118") (name "Net-(IC1-2IN-)") (class "Default")
      (node (ref "IC1") (pin "6") (pinfunction "2IN-_6") (pintype "input"))
      (node (ref "PH42") (pin "5") (pinfunction "5_5") (pintype "passive"))
    )
    (net (code "119") (name "Net-(IC1-2OUT)") (class "Default")
      (node (ref "IC1") (pin "7") (pinfunction "2OUT_7") (pintype "output"))
      (node (ref "PH44") (pin "6") (pinfunction "6_6") (pintype "passive"))
    )
    (net (code "120") (name "Net-(IC1-3IN+)") (class "Default")
      (node (ref "IC1") (pin "10") (pinfunction "3IN+_10") (pintype "input"))
      (node (ref "PH42") (pin "4") (pinfunction "4_4") (pintype "passive"))
    )
    (net (code "121") (name "Net-(IC1-3IN-)") (class "Default")
      (node (ref "IC1") (pin "9") (pinfunction "3IN-_9") (pintype "input"))
      (node (ref "PH42") (pin "3") (pinfunction "3_3") (pintype "passive"))
    )
    (net (code "122") (name "Net-(IC1-3OUT)") (class "Default")
      (node (ref "IC1") (pin "8") (pinfunction "3OUT_8") (pintype "output"))
      (node (ref "PH44") (pin "7") (pinfunction "7_7") (pintype "passive"))
    )
    (net (code "123") (name "Net-(IC1-4IN+)") (class "Default")
      (node (ref "IC1") (pin "12") (pinfunction "4IN+_12") (pintype "input"))
      (node (ref "PH42") (pin "2") (pinfunction "2_2") (pintype "passive"))
    )
    (net (code "124") (name "Net-(IC1-4IN-)") (class "Default")
      (node (ref "IC1") (pin "13") (pinfunction "4IN-_13") (pintype "input"))
      (node (ref "PH42") (pin "1") (pinfunction "1_1") (pintype "passive"))
    )
    (net (code "125") (name "Net-(IC1-4OUT)") (class "Default")
      (node (ref "IC1") (pin "14") (pinfunction "4OUT_14") (pintype "output"))
      (node (ref "PH44") (pin "8") (pinfunction "8_8") (pintype "passive"))
    )
    (net (code "126") (name "Net-(IC2-1IN+)") (class "Default")
      (node (ref "IC2") (pin "3") (pinfunction "1IN+_3") (pintype "input"))
      (node (ref "PH43") (pin "8") (pinfunction "8_8") (pintype "passive"))
    )
    (net (code "127") (name "Net-(IC2-1IN-)") (class "Default")
      (node (ref "IC2") (pin "2") (pinfunction "1IN-_2") (pintype "input"))
      (node (ref "PH43") (pin "7") (pinfunction "7_7") (pintype "passive"))
    )
    (net (code "128") (name "Net-(IC2-1OUT)") (class "Default")
      (node (ref "IC2") (pin "1") (pinfunction "1OUT_1") (pintype "output"))
      (node (ref "PH44") (pin "1") (pinfunction "1_1") (pintype "passive"))
    )
    (net (code "129") (name "Net-(IC2-2IN+)") (class "Default")
      (node (ref "IC2") (pin "5") (pinfunction "2IN+_5") (pintype "input"))
      (node (ref "PH43") (pin "6") (pinfunction "6_6") (pintype "passive"))
    )
    (net (code "130") (name "Net-(IC2-2IN-)") (class "Default")
      (node (ref "IC2") (pin "6") (pinfunction "2IN-_6") (pintype "input"))
      (node (ref "PH43") (pin "5") (pinfunction "5_5") (pintype "passive"))
    )
    (net (code "131") (name "Net-(IC2-2OUT)") (class "Default")
      (node (ref "IC2") (pin "7") (pinfunction "2OUT_7") (pintype "output"))
      (node (ref "PH44") (pin "2") (pinfunction "2_2") (pintype "passive"))
    )
    (net (code "132") (name "Net-(IC2-3IN+)") (class "Default")
      (node (ref "IC2") (pin "10") (pinfunction "3IN+_10") (pintype "input"))
      (node (ref "PH43") (pin "4") (pinfunction "4_4") (pintype "passive"))
    )
    (net (code "133") (name "Net-(IC2-3IN-)") (class "Default")
      (node (ref "IC2") (pin "9") (pinfunction "3IN-_9") (pintype "input"))
      (node (ref "PH43") (pin "3") (pinfunction "3_3") (pintype "passive"))
    )
    (net (code "134") (name "Net-(IC2-3OUT)") (class "Default")
      (node (ref "IC2") (pin "8") (pinfunction "3OUT_8") (pintype "output"))
      (node (ref "PH44") (pin "3") (pinfunction "3_3") (pintype "passive"))
    )
    (net (code "135") (name "Net-(IC2-4IN+)") (class "Default")
      (node (ref "IC2") (pin "12") (pinfunction "4IN+_12") (pintype "input"))
      (node (ref "PH43") (pin "2") (pinfunction "2_2") (pintype "passive"))
    )
    (net (code "136") (name "Net-(IC2-4IN-)") (class "Default")
      (node (ref "IC2") (pin "13") (pinfunction "4IN-_13") (pintype "input"))
      (node (ref "PH43") (pin "1") (pinfunction "1_1") (pintype "passive"))
    )
    (net (code "137") (name "Net-(IC2-4OUT)") (class "Default")
      (node (ref "IC2") (pin "14") (pinfunction "4OUT_14") (pintype "output"))
      (node (ref "PH44") (pin "4") (pinfunction "4_4") (pintype "passive"))
    )
    (net (code "138") (name "Net-(IC6A-CLK)") (class "Default")
      (node (ref "IC6") (pin "3") (pinfunction "CLK_3") (pintype "input"))
      (node (ref "PH27") (pin "2") (pinfunction "2_2") (pintype "passive"))
    )
    (net (code "139") (name "Net-(IC6A-J)") (class "Default")
      (node (ref "IC6") (pin "6") (pinfunction "J_6") (pintype "input"))
      (node (ref "PH27") (pin "3") (pinfunction "3_3") (pintype "passive"))
    )
    (net (code "140") (name "Net-(IC6A-K)") (class "Default")
      (node (ref "IC6") (pin "5") (pinfunction "K_5") (pintype "input"))
      (node (ref "PH27") (pin "1") (pinfunction "1_1") (pintype "passive"))
    )
    (net (code "141") (name "Net-(IC6A-Q)") (class "Default")
      (node (ref "IC6") (pin "1") (pinfunction "Q_1") (pintype "output"))
      (node (ref "PH9") (pin "2") (pinfunction "2_2") (pintype "passive"))
    )
    (net (code "142") (name "Net-(IC6A-~{Q})") (class "Default")
      (node (ref "IC6") (pin "2") (pinfunction "~{Q}_2") (pintype "output"))
      (node (ref "PH9") (pin "1") (pinfunction "1_1") (pintype "passive"))
    )
    (net (code "143") (name "Net-(IC6B-CLK)") (class "Default")
      (node (ref "IC6") (pin "13") (pinfunction "CLK_13") (pintype "input"))
      (node (ref "PH25") (pin "2") (pinfunction "2_2") (pintype "passive"))
    )
    (net (code "144") (name "Net-(IC6B-J)") (class "Default")
      (node (ref "IC6") (pin "10") (pinfunction "J_10") (pintype "input"))
      (node (ref "PH25") (pin "3") (pinfunction "3_3") (pintype "passive"))
    )
    (net (code "145") (name "Net-(IC6B-K)") (class "Default")
      (node (ref "IC6") (pin "11") (pinfunction "K_11") (pintype "input"))
      (node (ref "PH25") (pin "1") (pinfunction "1_1") (pintype "passive"))
    )
    (net (code "146") (name "Net-(IC6B-Q)") (class "Default")
      (node (ref "IC6") (pin "15") (pinfunction "Q_15") (pintype "output"))
      (node (ref "PH7") (pin "2") (pinfunction "2_2") (pintype "passive"))
    )
    (net (code "147") (name "Net-(IC6B-~{Q})") (class "Default")
      (node (ref "IC6") (pin "14") (pinfunction "~{Q}_14") (pintype "output"))
      (node (ref "PH7") (pin "1") (pinfunction "1_1") (pintype "passive"))
    )
    (net (code "148") (name "Net-(IC7A-CLK)") (class "Default")
      (node (ref "IC7") (pin "3") (pinfunction "CLK_3") (pintype "input"))
      (node (ref "PH28") (pin "2") (pinfunction "2_2") (pintype "passive"))
    )
    (net (code "149") (name "Net-(IC7A-J)") (class "Default")
      (node (ref "IC7") (pin "6") (pinfunction "J_6") (pintype "input"))
      (node (ref "PH28") (pin "3") (pinfunction "3_3") (pintype "passive"))
    )
    (net (code "150") (name "Net-(IC7A-K)") (class "Default")
      (node (ref "IC7") (pin "5") (pinfunction "K_5") (pintype "input"))
      (node (ref "PH28") (pin "1") (pinfunction "1_1") (pintype "passive"))
    )
    (net (code "151") (name "Net-(IC7A-Q)") (class "Default")
      (node (ref "IC7") (pin "1") (pinfunction "Q_1") (pintype "output"))
      (node (ref "PH10") (pin "2") (pinfunction "2_2") (pintype "passive"))
    )
    (net (code "152") (name "Net-(IC7A-~{Q})") (class "Default")
      (node (ref "IC7") (pin "2") (pinfunction "~{Q}_2") (pintype "output"))
      (node (ref "PH10") (pin "1") (pinfunction "1_1") (pintype "passive"))
    )
    (net (code "153") (name "Net-(IC7B-CLK)") (class "Default")
      (node (ref "IC7") (pin "13") (pinfunction "CLK_13") (pintype "input"))
      (node (ref "PH26") (pin "2") (pinfunction "2_2") (pintype "passive"))
    )
    (net (code "154") (name "Net-(IC7B-J)") (class "Default")
      (node (ref "IC7") (pin "10") (pinfunction "J_10") (pintype "input"))
      (node (ref "PH26") (pin "3") (pinfunction "3_3") (pintype "passive"))
    )
    (net (code "155") (name "Net-(IC7B-K)") (class "Default")
      (node (ref "IC7") (pin "11") (pinfunction "K_11") (pintype "input"))
      (node (ref "PH26") (pin "1") (pinfunction "1_1") (pintype "passive"))
    )
    (net (code "156") (name "Net-(IC7B-Q)") (class "Default")
      (node (ref "IC7") (pin "15") (pinfunction "Q_15") (pintype "output"))
      (node (ref "PH8") (pin "2") (pinfunction "2_2") (pintype "passive"))
    )
    (net (code "157") (name "Net-(IC7B-~{Q})") (class "Default")
      (node (ref "IC7") (pin "14") (pinfunction "~{Q}_14") (pintype "output"))
      (node (ref "PH8") (pin "1") (pinfunction "1_1") (pintype "passive"))
    )
    (net (code "158") (name "Net-(IC8-CV)") (class "Default")
      (node (ref "C21") (pin "1") (pinfunction "1_1") (pintype "passive"))
      (node (ref "IC8") (pin "5") (pinfunction "CV_5") (pintype "input"))
    )
    (net (code "159") (name "Net-(IC8-DIS)") (class "Default")
      (node (ref "IC8") (pin "7") (pinfunction "DIS_7") (pintype "input"))
      (node (ref "PH29") (pin "2") (pinfunction "2_2") (pintype "passive"))
    )
    (net (code "160") (name "Net-(IC8-Q)") (class "Default")
      (node (ref "IC8") (pin "3") (pinfunction "Q_3") (pintype "output"))
      (node (ref "PH1") (pin "1") (pinfunction "1_1") (pintype "passive"))
      (node (ref "R39") (pin "2") (pinfunction "2_2") (pintype "passive"))
    )
    (net (code "161") (name "Net-(IC8-THR)") (class "Default")
      (node (ref "IC8") (pin "6") (pinfunction "THR_6") (pintype "input"))
      (node (ref "PH29") (pin "3") (pinfunction "3_3") (pintype "passive"))
    )
    (net (code "162") (name "Net-(IC8-TR)") (class "Default")
      (node (ref "IC8") (pin "2") (pinfunction "TR_2") (pintype "input"))
      (node (ref "PH29") (pin "1") (pinfunction "1_1") (pintype "passive"))
    )
    (net (code "163") (name "Net-(JC1-Pad1)") (class "Default")
      (node (ref "JC1") (pin "1") (pinfunction "1_1") (pintype "bidirectional"))
      (node (ref "PH12") (pin "3") (pinfunction "3_3") (pintype "passive"))
    )
    (net (code "164") (name "Net-(JC1-Pad2)") (class "Default")
      (node (ref "JC1") (pin "2") (pinfunction "2_2") (pintype "bidirectional"))
      (node (ref "PH12") (pin "2") (pinfunction "2_2") (pintype "passive"))
    )
    (net (code "165") (name "Net-(JC1-Pad3)") (class "Default")
      (node (ref "JC1") (pin "3") (pinfunction "3_3") (pintype "bidirectional"))
      (node (ref "PH12") (pin "1") (pinfunction "1_1") (pintype "passive"))
    )
    (net (code "166") (name "Net-(JC2-Pad1)") (class "Default")
      (node (ref "JC2") (pin "1") (pinfunction "1_1") (pintype "bidirectional"))
      (node (ref "PH64") (pin "3") (pinfunction "3_3") (pintype "passive"))
    )
    (net (code "167") (name "Net-(JC2-Pad2)") (class "Default")
      (node (ref "JC2") (pin "2") (pinfunction "2_2") (pintype "bidirectional"))
      (node (ref "PH64") (pin "2") (pinfunction "2_2") (pintype "passive"))
    )
    (net (code "168") (name "Net-(JC2-Pad3)") (class "Default")
      (node (ref "JC2") (pin "3") (pinfunction "3_3") (pintype "bidirectional"))
      (node (ref "PH64") (pin "1") (pinfunction "1_1") (pintype "passive"))
    )
    (net (code "169") (name "Net-(L0-PadA)") (class "Default")
      (node (ref "L0") (pin "A") (pinfunction "A_A") (pintype "passive"))
      (node (ref "R31") (pin "2") (pinfunction "2_2") (pintype "passive"))
    )
    (net (code "170") (name "Net-(L1-PadA)") (class "Default")
      (node (ref "L1") (pin "A") (pinfunction "A_A") (pintype "passive"))
      (node (ref "R32") (pin "1") (pinfunction "1_1") (pintype "passive"))
    )
    (net (code "171") (name "Net-(L2-PadA)") (class "Default")
      (node (ref "L2") (pin "A") (pinfunction "A_A") (pintype "passive"))
      (node (ref "R33") (pin "1") (pinfunction "1_1") (pintype "passive"))
    )
    (net (code "172") (name "Net-(L3-PadA)") (class "Default")
      (node (ref "L3") (pin "A") (pinfunction "A_A") (pintype "passive"))
      (node (ref "R34") (pin "1") (pinfunction "1_1") (pintype "passive"))
    )
    (net (code "173") (name "Net-(L4-PadA)") (class "Default")
      (node (ref "L4") (pin "A") (pinfunction "A_A") (pintype "passive"))
      (node (ref "R35") (pin "1") (pinfunction "1_1") (pintype "passive"))
    )
    (net (code "174") (name "Net-(L5-PadA)") (class "Default")
      (node (ref "L5") (pin "A") (pinfunction "A_A") (pintype "passive"))
      (node (ref "R36") (pin "1") (pinfunction "1_1") (pintype "passive"))
    )
    (net (code "175") (name "Net-(L6-PadA)") (class "Default")
      (node (ref "L6") (pin "A") (pinfunction "A_A") (pintype "passive"))
      (node (ref "R37") (pin "1") (pinfunction "1_1") (pintype "passive"))
    )
    (net (code "176") (name "Net-(L7-PadA)") (class "Default")
      (node (ref "L7") (pin "A") (pinfunction "A_A") (pintype "passive"))
      (node (ref "R38") (pin "1") (pinfunction "1_1") (pintype "passive"))
    )
    (net (code "177") (name "Net-(L8-PadA)") (class "Default")
      (node (ref "L8") (pin "A") (pinfunction "A_A") (pintype "passive"))
      (node (ref "R48") (pin "1") (pinfunction "1_1") (pintype "passive"))
    )
    (net (code "178") (name "Net-(L9-PadA)") (class "Default")
      (node (ref "L9") (pin "A") (pinfunction "A_A") (pintype "passive"))
      (node (ref "R49") (pin "1") (pinfunction "1_1") (pintype "passive"))
    )
    (net (code "179") (name "Net-(L10-PadA)") (class "Default")
      (node (ref "L10") (pin "A") (pinfunction "A_A") (pintype "passive"))
      (node (ref "R50") (pin "1") (pinfunction "1_1") (pintype "passive"))
    )
    (net (code "180") (name "Net-(L11-PadA)") (class "Default")
      (node (ref "L11") (pin "A") (pinfunction "A_A") (pintype "passive"))
      (node (ref "R51") (pin "1") (pinfunction "1_1") (pintype "passive"))
    )
    (net (code "181") (name "Net-(L12-PadA)") (class "Default")
      (node (ref "L12") (pin "A") (pinfunction "A_A") (pintype "passive"))
      (node (ref "R52") (pin "1") (pinfunction "1_1") (pintype "passive"))
    )
    (net (code "182") (name "Net-(L13-PadA)") (class "Default")
      (node (ref "L13") (pin "A") (pinfunction "A_A") (pintype "passive"))
      (node (ref "R53") (pin "1") (pinfunction "1_1") (pintype "passive"))
    )
    (net (code "183") (name "Net-(L14-PadA)") (class "Default")
      (node (ref "L14") (pin "A") (pinfunction "A_A") (pintype "passive"))
      (node (ref "R54") (pin "1") (pinfunction "1_1") (pintype "passive"))
    )
    (net (code "184") (name "Net-(L15-PadA)") (class "Default")
      (node (ref "L15") (pin "A") (pinfunction "A_A") (pintype "passive"))
      (node (ref "R55") (pin "1") (pinfunction "1_1") (pintype "passive"))
    )
    (net (code "185") (name "Net-(L16-PadA)") (class "Default")
      (node (ref "L16") (pin "A") (pinfunction "A_A") (pintype "passive"))
      (node (ref "R56") (pin "1") (pinfunction "1_1") (pintype "passive"))
    )
    (net (code "186") (name "Net-(L17-PadA)") (class "Default")
      (node (ref "L17") (pin "A") (pinfunction "A_A") (pintype "passive"))
      (node (ref "R39") (pin "1") (pinfunction "1_1") (pintype "passive"))
    )
    (net (code "187") (name "Net-(LDR-Pad1)") (class "Default")
      (node (ref "LDR") (pin "1") (pinfunction "1_1") (pintype "passive"))
      (node (ref "PH5") (pin "1") (pinfunction "1_1") (pintype "passive"))
    )
    (net (code "188") (name "Net-(LDR-Pad2)") (class "Default")
      (node (ref "LDR") (pin "2") (pinfunction "2_2") (pintype "passive"))
      (node (ref "PH5") (pin "2") (pinfunction "2_2") (pintype "passive"))
    )
    (net (code "189") (name "Net-(LED_A-A)") (class "Default")
      (node (ref "LED_") (pin "3") (pinfunction "A_3") (pintype "passive"))
      (node (ref "R59") (pin "1") (pinfunction "1_1") (pintype "passive"))
    )
    (net (code "190") (name "Net-(LED_B-A)") (class "Default")
      (node (ref "LED_") (pin "2") (pinfunction "A_2") (pintype "passive"))
      (node (ref "R58") (pin "1") (pinfunction "1_1") (pintype "passive"))
    )
    (net (code "191") (name "Net-(LED_C-A)") (class "Default")
      (node (ref "LED_") (pin "1") (pinfunction "A_1") (pintype "passive"))
      (node (ref "R57") (pin "1") (pinfunction "1_1") (pintype "passive"))
    )
    (net (code "192") (name "Net-(MIC-Pad1)") (class "Default")
      (node (ref "MIC") (pin "1") (pinfunction "1_1") (pintype "passive"))
      (node (ref "PH4") (pin "2") (pinfunction "2_2") (pintype "passive"))
    )
    (net (code "193") (name "Net-(MIC-Pad2)") (class "Default")
      (node (ref "MIC") (pin "2") (pinfunction "2_2") (pintype "passive"))
      (node (ref "PH4") (pin "1") (pinfunction "1_1") (pintype "passive"))
    )
    (net (code "194") (name "Net-(NTC-Pad1)") (class "Default")
      (node (ref "NTC") (pin "1") (pinfunction "1_1") (pintype "passive"))
      (node (ref "PH6") (pin "2") (pinfunction "2_2") (pintype "passive"))
    )
    (net (code "195") (name "Net-(NTC-Pad2)") (class "Default")
      (node (ref "NTC") (pin "2") (pinfunction "2_2") (pintype "passive"))
      (node (ref "PH6") (pin "1") (pinfunction "1_1") (pintype "passive"))
    )
    (net (code "196") (name "Net-(P1-Pad1)") (class "Default")
      (node (ref "P1") (pin "1") (pinfunction "1_1") (pintype "passive"))
      (node (ref "PH24") (pin "3") (pinfunction "3_3") (pintype "passive"))
    )
    (net (code "197") (name "Net-(P1-Pad2)") (class "Default")
      (node (ref "P1") (pin "2") (pinfunction "2_2") (pintype "passive"))
      (node (ref "PH24") (pin "2") (pinfunction "2_2") (pintype "passive"))
    )
    (net (code "198") (name "Net-(P1-Pad3)") (class "Default")
      (node (ref "P1") (pin "3") (pinfunction "3_3") (pintype "passive"))
      (node (ref "PH24") (pin "1") (pinfunction "1_1") (pintype "passive"))
    )
    (net (code "199") (name "Net-(P2-Pad1)") (class "Default")
      (node (ref "P2") (pin "1") (pinfunction "1_1") (pintype "passive"))
      (node (ref "PH22") (pin "3") (pinfunction "3_3") (pintype "passive"))
    )
    (net (code "200") (name "Net-(P2-Pad2)") (class "Default")
      (node (ref "P2") (pin "2") (pinfunction "2_2") (pintype "passive"))
      (node (ref "PH22") (pin "2") (pinfunction "2_2") (pintype "passive"))
    )
    (net (code "201") (name "Net-(P2-Pad3)") (class "Default")
      (node (ref "P2") (pin "3") (pinfunction "3_3") (pintype "passive"))
      (node (ref "PH22") (pin "1") (pinfunction "1_1") (pintype "passive"))
    )
    (net (code "202") (name "Net-(P3-Pad1)") (class "Default")
      (node (ref "P3") (pin "1") (pinfunction "1_1") (pintype "passive"))
      (node (ref "PH23") (pin "3") (pinfunction "3_3") (pintype "passive"))
    )
    (net (code "203") (name "Net-(P3-Pad2)") (class "Default")
      (node (ref "P3") (pin "2") (pinfunction "2_2") (pintype "passive"))
      (node (ref "PH23") (pin "2") (pinfunction "2_2") (pintype "passive"))
    )
    (net (code "204") (name "Net-(P3-Pad3)") (class "Default")
      (node (ref "P3") (pin "3") (pinfunction "3_3") (pintype "passive"))
      (node (ref "PH23") (pin "1") (pinfunction "1_1") (pintype "passive"))
    )
    (net (code "205") (name "Net-(PB1-A0)") (class "Default")
      (node (ref "PB1") (pin "1") (pinfunction "A0_1") (pintype "bidirectional"))
      (node (ref "PB1") (pin "2") (pinfunction "A1_2") (pintype "bidirectional"))
      (node (ref "PB2") (pin "1") (pinfunction "A0_1") (pintype "bidirectional"))
      (node (ref "PB2") (pin "2") (pinfunction "A1_2") (pintype "bidirectional"))
      (node (ref "PB3") (pin "1") (pinfunction "A0_1") (pintype "bidirectional"))
      (node (ref "PB3") (pin "2") (pinfunction "A1_2") (pintype "bidirectional"))
      (node (ref "PH19") (pin "3") (pinfunction "3_3") (pintype "passive"))
    )
    (net (code "206") (name "Net-(PB1-B0)") (class "Default")
      (node (ref "PB1") (pin "3") (pinfunction "B0_3") (pintype "bidirectional"))
      (node (ref "PB1") (pin "4") (pinfunction "B1_4") (pintype "bidirectional"))
      (node (ref "PB4") (pin "3") (pinfunction "B0_3") (pintype "bidirectional"))
      (node (ref "PB4") (pin "4") (pinfunction "B1_4") (pintype "bidirectional"))
      (node (ref "PB7") (pin "3") (pinfunction "B0_3") (pintype "bidirectional"))
      (node (ref "PB7") (pin "4") (pinfunction "B1_4") (pintype "bidirectional"))
      (node (ref "PH20") (pin "1") (pinfunction "1_1") (pintype "passive"))
    )
    (net (code "207") (name "Net-(PB2-B0)") (class "Default")
      (node (ref "PB2") (pin "3") (pinfunction "B0_3") (pintype "bidirectional"))
      (node (ref "PB2") (pin "4") (pinfunction "B1_4") (pintype "bidirectional"))
      (node (ref "PB5") (pin "3") (pinfunction "B0_3") (pintype "bidirectional"))
      (node (ref "PB5") (pin "4") (pinfunction "B1_4") (pintype "bidirectional"))
      (node (ref "PB8") (pin "3") (pinfunction "B0_3") (pintype "bidirectional"))
      (node (ref "PB8") (pin "4") (pinfunction "B1_4") (pintype "bidirectional"))
      (node (ref "PH20") (pin "2") (pinfunction "2_2") (pintype "passive"))
    )
    (net (code "208") (name "Net-(PB3-B0)") (class "Default")
      (node (ref "PB3") (pin "3") (pinfunction "B0_3") (pintype "bidirectional"))
      (node (ref "PB3") (pin "4") (pinfunction "B1_4") (pintype "bidirectional"))
      (node (ref "PB6") (pin "3") (pinfunction "B0_3") (pintype "bidirectional"))
      (node (ref "PB6") (pin "4") (pinfunction "B1_4") (pintype "bidirectional"))
      (node (ref "PB9") (pin "3") (pinfunction "B0_3") (pintype "bidirectional"))
      (node (ref "PB9") (pin "4") (pinfunction "B1_4") (pintype "bidirectional"))
      (node (ref "PH20") (pin "3") (pinfunction "3_3") (pintype "passive"))
    )
    (net (code "209") (name "Net-(PB4-A0)") (class "Default")
      (node (ref "PB4") (pin "1") (pinfunction "A0_1") (pintype "bidirectional"))
      (node (ref "PB4") (pin "2") (pinfunction "A1_2") (pintype "bidirectional"))
      (node (ref "PB5") (pin "1") (pinfunction "A0_1") (pintype "bidirectional"))
      (node (ref "PB5") (pin "2") (pinfunction "A1_2") (pintype "bidirectional"))
      (node (ref "PB6") (pin "1") (pinfunction "A0_1") (pintype "bidirectional"))
      (node (ref "PB6") (pin "2") (pinfunction "A1_2") (pintype "bidirectional"))
      (node (ref "PH19") (pin "2") (pinfunction "2_2") (pintype "passive"))
    )
    (net (code "210") (name "Net-(PB7-A0)") (class "Default")
      (node (ref "PB7") (pin "1") (pinfunction "A0_1") (pintype "bidirectional"))
      (node (ref "PB7") (pin "2") (pinfunction "A1_2") (pintype "bidirectional"))
      (node (ref "PB8") (pin "1") (pinfunction "A0_1") (pintype "bidirectional"))
      (node (ref "PB8") (pin "2") (pinfunction "A1_2") (pintype "bidirectional"))
      (node (ref "PB9") (pin "1") (pinfunction "A0_1") (pintype "bidirectional"))
      (node (ref "PB9") (pin "2") (pinfunction "A1_2") (pintype "bidirectional"))
      (node (ref "PH19") (pin "1") (pinfunction "1_1") (pintype "passive"))
    )
    (net (code "211") (name "Net-(PH2-Pad1)") (class "Default")
      (node (ref "PH2") (pin "1") (pinfunction "1_1") (pintype "passive"))
      (node (ref "SP1") (pin "+") (pinfunction "+_+") (pintype "bidirectional"))
    )
    (net (code "212") (name "Net-(PH2-Pad2)") (class "Default")
      (node (ref "PH2") (pin "2") (pinfunction "2_2") (pintype "passive"))
      (node (ref "SP1") (pin "-") (pinfunction "-_-") (pintype "bidirectional"))
    )
    (net (code "213") (name "Net-(PH14-Pad1)") (class "Default")
      (node (ref "PH14") (pin "1") (pinfunction "1_1") (pintype "passive"))
      (node (ref "T4") (pin "C") (pinfunction "C_C") (pintype "passive"))
    )
    (net (code "214") (name "Net-(PH14-Pad2)") (class "Default")
      (node (ref "PH14") (pin "2") (pinfunction "2_2") (pintype "passive"))
      (node (ref "T4") (pin "B") (pinfunction "B_B") (pintype "passive"))
    )
    (net (code "215") (name "Net-(PH14-Pad3)") (class "Default")
      (node (ref "PH14") (pin "3") (pinfunction "3_3") (pintype "passive"))
      (node (ref "T4") (pin "E") (pinfunction "E_E") (pintype "passive"))
    )
    (net (code "216") (name "Net-(PH15-Pad1)") (class "Default")
      (node (ref "PH15") (pin "1") (pinfunction "1_1") (pintype "passive"))
      (node (ref "T5") (pin "C") (pinfunction "C_C") (pintype "passive"))
    )
    (net (code "217") (name "Net-(PH15-Pad2)") (class "Default")
      (node (ref "PH15") (pin "2") (pinfunction "2_2") (pintype "passive"))
      (node (ref "T5") (pin "B") (pinfunction "B_B") (pintype "passive"))
    )
    (net (code "218") (name "Net-(PH15-Pad3)") (class "Default")
      (node (ref "PH15") (pin "3") (pinfunction "3_3") (pintype "passive"))
      (node (ref "T5") (pin "E") (pinfunction "E_E") (pintype "passive"))
    )
    (net (code "219") (name "Net-(PH16-Pad1)") (class "Default")
      (node (ref "PH16") (pin "1") (pinfunction "1_1") (pintype "passive"))
      (node (ref "T1") (pin "E") (pinfunction "E_E") (pintype "passive"))
    )
    (net (code "220") (name "Net-(PH16-Pad2)") (class "Default")
      (node (ref "PH16") (pin "2") (pinfunction "2_2") (pintype "passive"))
      (node (ref "T1") (pin "B") (pinfunction "B_B") (pintype "passive"))
    )
    (net (code "221") (name "Net-(PH16-Pad3)") (class "Default")
      (node (ref "PH16") (pin "3") (pinfunction "3_3") (pintype "passive"))
      (node (ref "T1") (pin "C") (pinfunction "C_C") (pintype "passive"))
    )
    (net (code "222") (name "Net-(PH17-Pad1)") (class "Default")
      (node (ref "PH17") (pin "1") (pinfunction "1_1") (pintype "passive"))
      (node (ref "T2") (pin "E") (pinfunction "E_E") (pintype "passive"))
    )
    (net (code "223") (name "Net-(PH17-Pad2)") (class "Default")
      (node (ref "PH17") (pin "2") (pinfunction "2_2") (pintype "passive"))
      (node (ref "T2") (pin "B") (pinfunction "B_B") (pintype "passive"))
    )
    (net (code "224") (name "Net-(PH17-Pad3)") (class "Default")
      (node (ref "PH17") (pin "3") (pinfunction "3_3") (pintype "passive"))
      (node (ref "T2") (pin "C") (pinfunction "C_C") (pintype "passive"))
    )
    (net (code "225") (name "Net-(PH18-Pad1)") (class "Default")
      (node (ref "PH18") (pin "1") (pinfunction "1_1") (pintype "passive"))
      (node (ref "T3") (pin "E") (pinfunction "E_E") (pintype "passive"))
    )
    (net (code "226") (name "Net-(PH18-Pad2)") (class "Default")
      (node (ref "PH18") (pin "2") (pinfunction "2_2") (pintype "passive"))
      (node (ref "T3") (pin "B") (pinfunction "B_B") (pintype "passive"))
    )
    (net (code "227") (name "Net-(PH18-Pad3)") (class "Default")
      (node (ref "PH18") (pin "3") (pinfunction "3_3") (pintype "passive"))
      (node (ref "T3") (pin "C") (pinfunction "C_C") (pintype "passive"))
    )
    (net (code "228") (name "Net-(PH21-Pad1)") (class "Default")
      (node (ref "PH21") (pin "1") (pinfunction "1_1") (pintype "passive"))
      (node (ref "U$16") (pin "0") (pinfunction "0_0") (pintype "bidirectional"))
    )
    (net (code "229") (name "Net-(PH21-Pad2)") (class "Default")
      (node (ref "PH21") (pin "2") (pinfunction "2_2") (pintype "passive"))
      (node (ref "U$16") (pin "1") (pinfunction "1_1") (pintype "bidirectional"))
    )
    (net (code "230") (name "Net-(PH31-Pad1)") (class "Default")
      (node (ref "PH31") (pin "1") (pinfunction "1_1") (pintype "passive"))
      (node (ref "PH59") (pin "1") (pinfunction "1_1") (pintype "passive"))
      (node (ref "PH60") (pin "1") (pinfunction "1_1") (pintype "passive"))
      (node (ref "PH61") (pin "1") (pinfunction "1_1") (pintype "passive"))
    )
    (net (code "231") (name "Net-(PH31-Pad2)") (class "Default")
      (node (ref "PH31") (pin "2") (pinfunction "2_2") (pintype "passive"))
      (node (ref "PH59") (pin "2") (pinfunction "2_2") (pintype "passive"))
      (node (ref "PH60") (pin "2") (pinfunction "2_2") (pintype "passive"))
      (node (ref "PH61") (pin "2") (pinfunction "2_2") (pintype "passive"))
    )
    (net (code "232") (name "Net-(PH31-Pad3)") (class "Default")
      (node (ref "PH31") (pin "3") (pinfunction "3_3") (pintype "passive"))
      (node (ref "PH59") (pin "3") (pinfunction "3_3") (pintype "passive"))
      (node (ref "PH60") (pin "3") (pinfunction "3_3") (pintype "passive"))
      (node (ref "PH61") (pin "3") (pinfunction "3_3") (pintype "passive"))
    )
    (net (code "233") (name "Net-(PH31-Pad4)") (class "Default")
      (node (ref "PH31") (pin "4") (pinfunction "4_4") (pintype "passive"))
      (node (ref "PH59") (pin "4") (pinfunction "4_4") (pintype "passive"))
      (node (ref "PH60") (pin "4") (pinfunction "4_4") (pintype "passive"))
      (node (ref "PH61") (pin "4") (pinfunction "4_4") (pintype "passive"))
    )
    (net (code "234") (name "Net-(PH31-Pad5)") (class "Default")
      (node (ref "PH31") (pin "5") (pinfunction "5_5") (pintype "passive"))
      (node (ref "PH59") (pin "5") (pinfunction "5_5") (pintype "passive"))
      (node (ref "PH60") (pin "5") (pinfunction "5_5") (pintype "passive"))
      (node (ref "PH61") (pin "5") (pinfunction "5_5") (pintype "passive"))
    )
    (net (code "235") (name "Net-(PH31-Pad6)") (class "Default")
      (node (ref "PH31") (pin "6") (pinfunction "6_6") (pintype "passive"))
      (node (ref "PH59") (pin "6") (pinfunction "6_6") (pintype "passive"))
      (node (ref "PH60") (pin "6") (pinfunction "6_6") (pintype "passive"))
      (node (ref "PH61") (pin "6") (pinfunction "6_6") (pintype "passive"))
    )
    (net (code "236") (name "Net-(PH31-Pad7)") (class "Default")
      (node (ref "PH31") (pin "7") (pinfunction "7_7") (pintype "passive"))
      (node (ref "PH59") (pin "7") (pinfunction "7_7") (pintype "passive"))
      (node (ref "PH60") (pin "7") (pinfunction "7_7") (pintype "passive"))
      (node (ref "PH61") (pin "7") (pinfunction "7_7") (pintype "passive"))
    )
    (net (code "237") (name "Net-(PH31-Pad8)") (class "Default")
      (node (ref "PH31") (pin "8") (pinfunction "8_8") (pintype "passive"))
      (node (ref "PH59") (pin "8") (pinfunction "8_8") (pintype "passive"))
      (node (ref "PH60") (pin "8") (pinfunction "8_8") (pintype "passive"))
      (node (ref "PH61") (pin "8") (pinfunction "8_8") (pintype "passive"))
    )
    (net (code "238") (name "Net-(PH31-Pad9)") (class "Default")
      (node (ref "PH31") (pin "9") (pinfunction "9_9") (pintype "passive"))
      (node (ref "PH59") (pin "9") (pinfunction "9_9") (pintype "passive"))
      (node (ref "PH60") (pin "9") (pinfunction "9_9") (pintype "passive"))
      (node (ref "PH61") (pin "9") (pinfunction "9_9") (pintype "passive"))
    )
    (net (code "239") (name "Net-(PH31-Pad10)") (class "Default")
      (node (ref "PH31") (pin "10") (pinfunction "10_10") (pintype "passive"))
      (node (ref "PH59") (pin "10") (pinfunction "10_10") (pintype "passive"))
      (node (ref "PH60") (pin "10") (pinfunction "10_10") (pintype "passive"))
      (node (ref "PH61") (pin "10") (pinfunction "10_10") (pintype "passive"))
    )
    (net (code "240") (name "Net-(PH31-Pad11)") (class "Default")
      (node (ref "PH31") (pin "11") (pinfunction "11_11") (pintype "passive"))
      (node (ref "PH59") (pin "11") (pinfunction "11_11") (pintype "passive"))
      (node (ref "PH60") (pin "11") (pinfunction "11_11") (pintype "passive"))
      (node (ref "PH61") (pin "11") (pinfunction "11_11") (pintype "passive"))
    )
    (net (code "241") (name "Net-(PH31-Pad12)") (class "Default")
      (node (ref "PH31") (pin "12") (pinfunction "12_12") (pintype "passive"))
      (node (ref "PH59") (pin "12") (pinfunction "12_12") (pintype "passive"))
      (node (ref "PH60") (pin "12") (pinfunction "12_12") (pintype "passive"))
      (node (ref "PH61") (pin "12") (pinfunction "12_12") (pintype "passive"))
    )
    (net (code "242") (name "Net-(PH31-Pad13)") (class "Default")
      (node (ref "PH31") (pin "13") (pinfunction "13_13") (pintype "passive"))
      (node (ref "PH59") (pin "13") (pinfunction "13_13") (pintype "passive"))
      (node (ref "PH60") (pin "13") (pinfunction "13_13") (pintype "passive"))
      (node (ref "PH61") (pin "13") (pinfunction "13_13") (pintype "passive"))
    )
    (net (code "243") (name "Net-(PH31-Pad14)") (class "Default")
      (node (ref "PH31") (pin "14") (pinfunction "14_14") (pintype "passive"))
      (node (ref "PH59") (pin "14") (pinfunction "14_14") (pintype "passive"))
      (node (ref "PH60") (pin "14") (pinfunction "14_14") (pintype "passive"))
      (node (ref "PH61") (pin "14") (pinfunction "14_14") (pintype "passive"))
    )
    (net (code "244") (name "Net-(PH31-Pad15)") (class "Default")
      (node (ref "PH31") (pin "15") (pinfunction "15_15") (pintype "passive"))
      (node (ref "PH59") (pin "15") (pinfunction "15_15") (pintype "passive"))
      (node (ref "PH60") (pin "15") (pinfunction "15_15") (pintype "passive"))
      (node (ref "PH61") (pin "15") (pinfunction "15_15") (pintype "passive"))
    )
    (net (code "245") (name "Net-(PH31-Pad16)") (class "Default")
      (node (ref "PH31") (pin "16") (pinfunction "16_16") (pintype "passive"))
      (node (ref "PH59") (pin "16") (pinfunction "16_16") (pintype "passive"))
      (node (ref "PH60") (pin "16") (pinfunction "16_16") (pintype "passive"))
      (node (ref "PH61") (pin "16") (pinfunction "16_16") (pintype "passive"))
    )
    (net (code "246") (name "Net-(PH31-Pad17)") (class "Default")
      (node (ref "PH31") (pin "17") (pinfunction "17_17") (pintype "passive"))
      (node (ref "PH59") (pin "17") (pinfunction "17_17") (pintype "passive"))
      (node (ref "PH60") (pin "17") (pinfunction "17_17") (pintype "passive"))
      (node (ref "PH61") (pin "17") (pinfunction "17_17") (pintype "passive"))
    )
    (net (code "247") (name "Net-(PH31-Pad18)") (class "Default")
      (node (ref "PH31") (pin "18") (pinfunction "18_18") (pintype "passive"))
      (node (ref "PH59") (pin "18") (pinfunction "18_18") (pintype "passive"))
      (node (ref "PH60") (pin "18") (pinfunction "18_18") (pintype "passive"))
      (node (ref "PH61") (pin "18") (pinfunction "18_18") (pintype "passive"))
    )
    (net (code "248") (name "Net-(PH31-Pad19)") (class "Default")
      (node (ref "PH31") (pin "19") (pinfunction "19_19") (pintype "passive"))
      (node (ref "PH59") (pin "19") (pinfunction "19_19") (pintype "passive"))
      (node (ref "PH60") (pin "19") (pinfunction "19_19") (pintype "passive"))
      (node (ref "PH61") (pin "19") (pinfunction "19_19") (pintype "passive"))
    )
    (net (code "249") (name "Net-(PH31-Pad20)") (class "Default")
      (node (ref "PH31") (pin "20") (pinfunction "20_20") (pintype "passive"))
      (node (ref "PH59") (pin "20") (pinfunction "20_20") (pintype "passive"))
      (node (ref "PH60") (pin "20") (pinfunction "20_20") (pintype "passive"))
      (node (ref "PH61") (pin "20") (pinfunction "20_20") (pintype "passive"))
    )
    (net (code "250") (name "Net-(PH31-Pad21)") (class "Default")
      (node (ref "PH31") (pin "21") (pinfunction "21_21") (pintype "passive"))
      (node (ref "PH59") (pin "21") (pinfunction "21_21") (pintype "passive"))
      (node (ref "PH60") (pin "21") (pinfunction "21_21") (pintype "passive"))
      (node (ref "PH61") (pin "21") (pinfunction "21_21") (pintype "passive"))
    )
    (net (code "251") (name "Net-(PH31-Pad22)") (class "Default")
      (node (ref "PH31") (pin "22") (pinfunction "22_22") (pintype "passive"))
      (node (ref "PH59") (pin "22") (pinfunction "22_22") (pintype "passive"))
      (node (ref "PH60") (pin "22") (pinfunction "22_22") (pintype "passive"))
      (node (ref "PH61") (pin "22") (pinfunction "22_22") (pintype "passive"))
    )
    (net (code "252") (name "Net-(PH31-Pad23)") (class "Default")
      (node (ref "PH31") (pin "23") (pinfunction "23_23") (pintype "passive"))
      (node (ref "PH59") (pin "23") (pinfunction "23_23") (pintype "passive"))
      (node (ref "PH60") (pin "23") (pinfunction "23_23") (pintype "passive"))
      (node (ref "PH61") (pin "23") (pinfunction "23_23") (pintype "passive"))
    )
    (net (code "253") (name "Net-(PH31-Pad24)") (class "Default")
      (node (ref "PH31") (pin "24") (pinfunction "24_24") (pintype "passive"))
      (node (ref "PH59") (pin "24") (pinfunction "24_24") (pintype "passive"))
      (node (ref "PH60") (pin "24") (pinfunction "24_24") (pintype "passive"))
      (node (ref "PH61") (pin "24") (pinfunction "24_24") (pintype "passive"))
    )
    (net (code "254") (name "Net-(PH31-Pad25)") (class "Default")
      (node (ref "PH31") (pin "25") (pinfunction "25_25") (pintype "passive"))
      (node (ref "PH59") (pin "25") (pinfunction "25_25") (pintype "passive"))
      (node (ref "PH60") (pin "25") (pinfunction "25_25") (pintype "passive"))
      (node (ref "PH61") (pin "25") (pinfunction "25_25") (pintype "passive"))
    )
    (net (code "255") (name "Net-(PH31-Pad26)") (class "Default")
      (node (ref "PH31") (pin "26") (pinfunction "26_26") (pintype "passive"))
      (node (ref "PH59") (pin "26") (pinfunction "26_26") (pintype "passive"))
      (node (ref "PH60") (pin "26") (pinfunction "26_26") (pintype "passive"))
      (node (ref "PH61") (pin "26") (pinfunction "26_26") (pintype "passive"))
    )
    (net (code "256") (name "Net-(PH31-Pad27)") (class "Default")
      (node (ref "PH31") (pin "27") (pinfunction "27_27") (pintype "passive"))
      (node (ref "PH59") (pin "27") (pinfunction "27_27") (pintype "passive"))
      (node (ref "PH60") (pin "27") (pinfunction "27_27") (pintype "passive"))
      (node (ref "PH61") (pin "27") (pinfunction "27_27") (pintype "passive"))
    )
    (net (code "257") (name "Net-(PH31-Pad28)") (class "Default")
      (node (ref "PH31") (pin "28") (pinfunction "28_28") (pintype "passive"))
      (node (ref "PH59") (pin "28") (pinfunction "28_28") (pintype "passive"))
      (node (ref "PH60") (pin "28") (pinfunction "28_28") (pintype "passive"))
      (node (ref "PH61") (pin "28") (pinfunction "28_28") (pintype "passive"))
    )
    (net (code "258") (name "Net-(PH31-Pad29)") (class "Default")
      (node (ref "PH31") (pin "29") (pinfunction "29_29") (pintype "passive"))
      (node (ref "PH59") (pin "29") (pinfunction "29_29") (pintype "passive"))
      (node (ref "PH60") (pin "29") (pinfunction "29_29") (pintype "passive"))
      (node (ref "PH61") (pin "29") (pinfunction "29_29") (pintype "passive"))
    )
    (net (code "259") (name "Net-(PH31-Pad30)") (class "Default")
      (node (ref "PH31") (pin "30") (pinfunction "30_30") (pintype "passive"))
      (node (ref "PH59") (pin "30") (pinfunction "30_30") (pintype "passive"))
      (node (ref "PH60") (pin "30") (pinfunction "30_30") (pintype "passive"))
      (node (ref "PH61") (pin "30") (pinfunction "30_30") (pintype "passive"))
    )
    (net (code "260") (name "Net-(PH34-Pad1)") (class "Default")
      (node (ref "PH34") (pin "1") (pinfunction "1_1") (pintype "passive"))
      (node (ref "R67") (pin "2") (pinfunction "2_2") (pintype "passive"))
      (node (ref "U2") (pin "B1") (pinfunction "B1_B1") (pintype "bidirectional"))
    )
    (net (code "261") (name "Net-(PH48-Pad1)") (class "Default")
      (node (ref "PH48") (pin "1") (pinfunction "1_1") (pintype "passive"))
      (node (ref "R28") (pin "1") (pinfunction "1_1") (pintype "passive"))
    )
    (net (code "262") (name "Net-(PH48-Pad2)") (class "Default")
      (node (ref "PH48") (pin "2") (pinfunction "2_2") (pintype "passive"))
      (node (ref "R25") (pin "1") (pinfunction "1_1") (pintype "passive"))
    )
    (net (code "263") (name "Net-(PH48-Pad3)") (class "Default")
      (node (ref "PH48") (pin "3") (pinfunction "3_3") (pintype "passive"))
      (node (ref "R22") (pin "1") (pinfunction "1_1") (pintype "passive"))
    )
    (net (code "264") (name "Net-(PH48-Pad4)") (class "Default")
      (node (ref "PH48") (pin "4") (pinfunction "4_4") (pintype "passive"))
      (node (ref "R19") (pin "1") (pinfunction "1_1") (pintype "passive"))
    )
    (net (code "265") (name "Net-(PH48-Pad5)") (class "Default")
      (node (ref "PH48") (pin "5") (pinfunction "5_5") (pintype "passive"))
      (node (ref "R16") (pin "1") (pinfunction "1_1") (pintype "passive"))
    )
    (net (code "266") (name "Net-(PH48-Pad6)") (class "Default")
      (node (ref "PH48") (pin "6") (pinfunction "6_6") (pintype "passive"))
      (node (ref "R13") (pin "1") (pinfunction "1_1") (pintype "passive"))
    )
    (net (code "267") (name "Net-(PH48-Pad7)") (class "Default")
      (node (ref "PH48") (pin "7") (pinfunction "7_7") (pintype "passive"))
      (node (ref "R10") (pin "1") (pinfunction "1_1") (pintype "passive"))
    )
    (net (code "268") (name "Net-(PH48-Pad8)") (class "Default")
      (node (ref "PH48") (pin "8") (pinfunction "8_8") (pintype "passive"))
      (node (ref "R7") (pin "1") (pinfunction "1_1") (pintype "passive"))
    )
    (net (code "269") (name "Net-(PH48-Pad9)") (class "Default")
      (node (ref "PH48") (pin "9") (pinfunction "9_9") (pintype "passive"))
      (node (ref "R4") (pin "1") (pinfunction "1_1") (pintype "passive"))
    )
    (net (code "270") (name "Net-(PH48-Pad10)") (class "Default")
      (node (ref "PH48") (pin "10") (pinfunction "10_10") (pintype "passive"))
      (node (ref "R1") (pin "1") (pinfunction "1_1") (pintype "passive"))
    )
    (net (code "271") (name "Net-(PH49-Pad1)") (class "Default")
      (node (ref "PH49") (pin "1") (pinfunction "1_1") (pintype "passive"))
      (node (ref "R1") (pin "2") (pinfunction "2_2") (pintype "passive"))
    )
    (net (code "272") (name "Net-(PH49-Pad2)") (class "Default")
      (node (ref "PH49") (pin "2") (pinfunction "2_2") (pintype "passive"))
      (node (ref "R4") (pin "2") (pinfunction "2_2") (pintype "passive"))
    )
    (net (code "273") (name "Net-(PH49-Pad3)") (class "Default")
      (node (ref "PH49") (pin "3") (pinfunction "3_3") (pintype "passive"))
      (node (ref "R7") (pin "2") (pinfunction "2_2") (pintype "passive"))
    )
    (net (code "274") (name "Net-(PH49-Pad4)") (class "Default")
      (node (ref "PH49") (pin "4") (pinfunction "4_4") (pintype "passive"))
      (node (ref "R10") (pin "2") (pinfunction "2_2") (pintype "passive"))
    )
    (net (code "275") (name "Net-(PH49-Pad5)") (class "Default")
      (node (ref "PH49") (pin "5") (pinfunction "5_5") (pintype "passive"))
      (node (ref "R13") (pin "2") (pinfunction "2_2") (pintype "passive"))
    )
    (net (code "276") (name "Net-(PH49-Pad6)") (class "Default")
      (node (ref "PH49") (pin "6") (pinfunction "6_6") (pintype "passive"))
      (node (ref "R16") (pin "2") (pinfunction "2_2") (pintype "passive"))
    )
    (net (code "277") (name "Net-(PH49-Pad7)") (class "Default")
      (node (ref "PH49") (pin "7") (pinfunction "7_7") (pintype "passive"))
      (node (ref "R19") (pin "2") (pinfunction "2_2") (pintype "passive"))
    )
    (net (code "278") (name "Net-(PH49-Pad8)") (class "Default")
      (node (ref "PH49") (pin "8") (pinfunction "8_8") (pintype "passive"))
      (node (ref "R22") (pin "2") (pinfunction "2_2") (pintype "passive"))
    )
    (net (code "279") (name "Net-(PH49-Pad9)") (class "Default")
      (node (ref "PH49") (pin "9") (pinfunction "9_9") (pintype "passive"))
      (node (ref "R25") (pin "2") (pinfunction "2_2") (pintype "passive"))
    )
    (net (code "280") (name "Net-(PH49-Pad10)") (class "Default")
      (node (ref "PH49") (pin "10") (pinfunction "10_10") (pintype "passive"))
      (node (ref "R28") (pin "2") (pinfunction "2_2") (pintype "passive"))
    )
    (net (code "281") (name "Net-(PH50-Pad1)") (class "Default")
      (node (ref "PH50") (pin "1") (pinfunction "1_1") (pintype "passive"))
      (node (ref "R29") (pin "1") (pinfunction "1_1") (pintype "passive"))
    )
    (net (code "282") (name "Net-(PH50-Pad2)") (class "Default")
      (node (ref "PH50") (pin "2") (pinfunction "2_2") (pintype "passive"))
      (node (ref "R26") (pin "1") (pinfunction "1_1") (pintype "passive"))
    )
    (net (code "283") (name "Net-(PH50-Pad3)") (class "Default")
      (node (ref "PH50") (pin "3") (pinfunction "3_3") (pintype "passive"))
      (node (ref "R23") (pin "1") (pinfunction "1_1") (pintype "passive"))
    )
    (net (code "284") (name "Net-(PH50-Pad4)") (class "Default")
      (node (ref "PH50") (pin "4") (pinfunction "4_4") (pintype "passive"))
      (node (ref "R20") (pin "1") (pinfunction "1_1") (pintype "passive"))
    )
    (net (code "285") (name "Net-(PH50-Pad5)") (class "Default")
      (node (ref "PH50") (pin "5") (pinfunction "5_5") (pintype "passive"))
      (node (ref "R17") (pin "1") (pinfunction "1_1") (pintype "passive"))
    )
    (net (code "286") (name "Net-(PH50-Pad6)") (class "Default")
      (node (ref "PH50") (pin "6") (pinfunction "6_6") (pintype "passive"))
      (node (ref "R14") (pin "1") (pinfunction "1_1") (pintype "passive"))
    )
    (net (code "287") (name "Net-(PH50-Pad7)") (class "Default")
      (node (ref "PH50") (pin "7") (pinfunction "7_7") (pintype "passive"))
      (node (ref "R11") (pin "1") (pinfunction "1_1") (pintype "passive"))
    )
    (net (code "288") (name "Net-(PH50-Pad8)") (class "Default")
      (node (ref "PH50") (pin "8") (pinfunction "8_8") (pintype "passive"))
      (node (ref "R8") (pin "1") (pinfunction "1_1") (pintype "passive"))
    )
    (net (code "289") (name "Net-(PH50-Pad9)") (class "Default")
      (node (ref "PH50") (pin "9") (pinfunction "9_9") (pintype "passive"))
      (node (ref "R5") (pin "1") (pinfunction "1_1") (pintype "passive"))
    )
    (net (code "290") (name "Net-(PH50-Pad10)") (class "Default")
      (node (ref "PH50") (pin "10") (pinfunction "10_10") (pintype "passive"))
      (node (ref "R2") (pin "1") (pinfunction "1_1") (pintype "passive"))
    )
    (net (code "291") (name "Net-(PH51-Pad1)") (class "Default")
      (node (ref "PH51") (pin "1") (pinfunction "1_1") (pintype "passive"))
      (node (ref "R2") (pin "2") (pinfunction "2_2") (pintype "passive"))
    )
    (net (code "292") (name "Net-(PH51-Pad2)") (class "Default")
      (node (ref "PH51") (pin "2") (pinfunction "2_2") (pintype "passive"))
      (node (ref "R5") (pin "2") (pinfunction "2_2") (pintype "passive"))
    )
    (net (code "293") (name "Net-(PH51-Pad3)") (class "Default")
      (node (ref "PH51") (pin "3") (pinfunction "3_3") (pintype "passive"))
      (node (ref "R8") (pin "2") (pinfunction "2_2") (pintype "passive"))
    )
    (net (code "294") (name "Net-(PH51-Pad4)") (class "Default")
      (node (ref "PH51") (pin "4") (pinfunction "4_4") (pintype "passive"))
      (node (ref "R11") (pin "2") (pinfunction "2_2") (pintype "passive"))
    )
    (net (code "295") (name "Net-(PH51-Pad5)") (class "Default")
      (node (ref "PH51") (pin "5") (pinfunction "5_5") (pintype "passive"))
      (node (ref "R14") (pin "2") (pinfunction "2_2") (pintype "passive"))
    )
    (net (code "296") (name "Net-(PH51-Pad6)") (class "Default")
      (node (ref "PH51") (pin "6") (pinfunction "6_6") (pintype "passive"))
      (node (ref "R17") (pin "2") (pinfunction "2_2") (pintype "passive"))
    )
    (net (code "297") (name "Net-(PH51-Pad7)") (class "Default")
      (node (ref "PH51") (pin "7") (pinfunction "7_7") (pintype "passive"))
      (node (ref "R20") (pin "2") (pinfunction "2_2") (pintype "passive"))
    )
    (net (code "298") (name "Net-(PH51-Pad8)") (class "Default")
      (node (ref "PH51") (pin "8") (pinfunction "8_8") (pintype "passive"))
      (node (ref "R23") (pin "2") (pinfunction "2_2") (pintype "passive"))
    )
    (net (code "299") (name "Net-(PH51-Pad9)") (class "Default")
      (node (ref "PH51") (pin "9") (pinfunction "9_9") (pintype "passive"))
      (node (ref "R26") (pin "2") (pinfunction "2_2") (pintype "passive"))
    )
    (net (code "300") (name "Net-(PH51-Pad10)") (class "Default")
      (node (ref "PH51") (pin "10") (pinfunction "10_10") (pintype "passive"))
      (node (ref "R29") (pin "2") (pinfunction "2_2") (pintype "passive"))
    )
    (net (code "301") (name "Net-(PH52-Pad1)") (class "Default")
      (node (ref "PH52") (pin "1") (pinfunction "1_1") (pintype "passive"))
      (node (ref "R30") (pin "1") (pinfunction "1_1") (pintype "passive"))
    )
    (net (code "302") (name "Net-(PH52-Pad2)") (class "Default")
      (node (ref "PH52") (pin "2") (pinfunction "2_2") (pintype "passive"))
      (node (ref "R27") (pin "1") (pinfunction "1_1") (pintype "passive"))
    )
    (net (code "303") (name "Net-(PH52-Pad3)") (class "Default")
      (node (ref "PH52") (pin "3") (pinfunction "3_3") (pintype "passive"))
      (node (ref "R24") (pin "1") (pinfunction "1_1") (pintype "passive"))
    )
    (net (code "304") (name "Net-(PH52-Pad4)") (class "Default")
      (node (ref "PH52") (pin "4") (pinfunction "4_4") (pintype "passive"))
      (node (ref "R21") (pin "1") (pinfunction "1_1") (pintype "passive"))
    )
    (net (code "305") (name "Net-(PH52-Pad5)") (class "Default")
      (node (ref "PH52") (pin "5") (pinfunction "5_5") (pintype "passive"))
      (node (ref "R18") (pin "1") (pinfunction "1_1") (pintype "passive"))
    )
    (net (code "306") (name "Net-(PH52-Pad6)") (class "Default")
      (node (ref "PH52") (pin "6") (pinfunction "6_6") (pintype "passive"))
      (node (ref "R15") (pin "1") (pinfunction "1_1") (pintype "passive"))
    )
    (net (code "307") (name "Net-(PH52-Pad7)") (class "Default")
      (node (ref "PH52") (pin "7") (pinfunction "7_7") (pintype "passive"))
      (node (ref "R12") (pin "1") (pinfunction "1_1") (pintype "passive"))
    )
    (net (code "308") (name "Net-(PH52-Pad8)") (class "Default")
      (node (ref "PH52") (pin "8") (pinfunction "8_8") (pintype "passive"))
      (node (ref "R9") (pin "1") (pinfunction "1_1") (pintype "passive"))
    )
    (net (code "309") (name "Net-(PH52-Pad9)") (class "Default")
      (node (ref "PH52") (pin "9") (pinfunction "9_9") (pintype "passive"))
      (node (ref "R6") (pin "1") (pinfunction "1_1") (pintype "passive"))
    )
    (net (code "310") (name "Net-(PH52-Pad10)") (class "Default")
      (node (ref "PH52") (pin "10") (pinfunction "10_10") (pintype "passive"))
      (node (ref "R3") (pin "1") (pinfunction "1_1") (pintype "passive"))
    )
    (net (code "311") (name "Net-(PH53-Pad1)") (class "Default")
      (node (ref "PH53") (pin "1") (pinfunction "1_1") (pintype "passive"))
      (node (ref "R3") (pin "2") (pinfunction "2_2") (pintype "passive"))
    )
    (net (code "312") (name "Net-(PH53-Pad2)") (class "Default")
      (node (ref "PH53") (pin "2") (pinfunction "2_2") (pintype "passive"))
      (node (ref "R6") (pin "2") (pinfunction "2_2") (pintype "passive"))
    )
    (net (code "313") (name "Net-(PH53-Pad3)") (class "Default")
      (node (ref "PH53") (pin "3") (pinfunction "3_3") (pintype "passive"))
      (node (ref "R9") (pin "2") (pinfunction "2_2") (pintype "passive"))
    )
    (net (code "314") (name "Net-(PH53-Pad4)") (class "Default")
      (node (ref "PH53") (pin "4") (pinfunction "4_4") (pintype "passive"))
      (node (ref "R12") (pin "2") (pinfunction "2_2") (pintype "passive"))
    )
    (net (code "315") (name "Net-(PH53-Pad5)") (class "Default")
      (node (ref "PH53") (pin "5") (pinfunction "5_5") (pintype "passive"))
      (node (ref "R15") (pin "2") (pinfunction "2_2") (pintype "passive"))
    )
    (net (code "316") (name "Net-(PH53-Pad6)") (class "Default")
      (node (ref "PH53") (pin "6") (pinfunction "6_6") (pintype "passive"))
      (node (ref "R18") (pin "2") (pinfunction "2_2") (pintype "passive"))
    )
    (net (code "317") (name "Net-(PH53-Pad7)") (class "Default")
      (node (ref "PH53") (pin "7") (pinfunction "7_7") (pintype "passive"))
      (node (ref "R21") (pin "2") (pinfunction "2_2") (pintype "passive"))
    )
    (net (code "318") (name "Net-(PH53-Pad8)") (class "Default")
      (node (ref "PH53") (pin "8") (pinfunction "8_8") (pintype "passive"))
      (node (ref "R24") (pin "2") (pinfunction "2_2") (pintype "passive"))
    )
    (net (code "319") (name "Net-(PH53-Pad9)") (class "Default")
      (node (ref "PH53") (pin "9") (pinfunction "9_9") (pintype "passive"))
      (node (ref "R27") (pin "2") (pinfunction "2_2") (pintype "passive"))
    )
    (net (code "320") (name "Net-(PH53-Pad10)") (class "Default")
      (node (ref "PH53") (pin "10") (pinfunction "10_10") (pintype "passive"))
      (node (ref "R30") (pin "2") (pinfunction "2_2") (pintype "passive"))
    )
    (net (code "321") (name "Net-(S1-LC)") (class "Default")
      (node (ref "F1") (pin "1") (pinfunction "1_1") (pintype "passive"))
      (node (ref "S1") (pin "2") (pinfunction "LC_2") (pintype "passive"))
    )
    (net (code "322") (name "O1A") (class "Default")
      (node (ref "AR2") (pin "9") (pinfunction "9_9") (pintype "bidirectional"))
      (node (ref "IC4") (pin "1") (pinfunction "1A_1") (pintype "input"))
      (node (ref "PH46") (pin "1") (pinfunction "1_1") (pintype "passive"))
    )
    (net (code "323") (name "O1B") (class "Default")
      (node (ref "AR2") (pin "8") (pinfunction "8_8") (pintype "bidirectional"))
      (node (ref "IC4") (pin "2") (pinfunction "1B_2") (pintype "input"))
      (node (ref "PH46") (pin "2") (pinfunction "2_2") (pintype "passive"))
    )
    (net (code "324") (name "O1Y") (class "Default")
      (node (ref "IC4") (pin "3") (pinfunction "1Y_3") (pintype "output"))
      (node (ref "PH37") (pin "1") (pinfunction "1_1") (pintype "passive"))
    )
    (net (code "325") (name "O2A") (class "Default")
      (node (ref "AR2") (pin "7") (pinfunction "7_7") (pintype "bidirectional"))
      (node (ref "IC4") (pin "4") (pinfunction "2A_4") (pintype "input"))
      (node (ref "PH46") (pin "3") (pinfunction "3_3") (pintype "passive"))
    )
    (net (code "326") (name "O2B") (class "Default")
      (node (ref "AR2") (pin "6") (pinfunction "6_6") (pintype "bidirectional"))
      (node (ref "IC4") (pin "5") (pinfunction "2B_5") (pintype "input"))
      (node (ref "PH46") (pin "4") (pinfunction "4_4") (pintype "passive"))
    )
    (net (code "327") (name "O2Y") (class "Default")
      (node (ref "IC4") (pin "6") (pinfunction "2Y_6") (pintype "output"))
      (node (ref "PH37") (pin "2") (pinfunction "2_2") (pintype "passive"))
    )
    (net (code "328") (name "O3A") (class "Default")
      (node (ref "AR2") (pin "1") (pinfunction "1_1") (pintype "bidirectional"))
      (node (ref "IC4") (pin "9") (pinfunction "3A_9") (pintype "input"))
      (node (ref "PH46") (pin "5") (pinfunction "5_5") (pintype "passive"))
    )
    (net (code "329") (name "O3B") (class "Default")
      (node (ref "AR2") (pin "2") (pinfunction "2_2") (pintype "bidirectional"))
      (node (ref "IC4") (pin "10") (pinfunction "3B_10") (pintype "input"))
      (node (ref "PH46") (pin "6") (pinfunction "6_6") (pintype "passive"))
    )
    (net (code "330") (name "O3Y") (class "Default")
      (node (ref "IC4") (pin "8") (pinfunction "3Y_8") (pintype "output"))
      (node (ref "PH37") (pin "3") (pinfunction "3_3") (pintype "passive"))
    )
    (net (code "331") (name "O4A") (class "Default")
      (node (ref "AR2") (pin "3") (pinfunction "3_3") (pintype "bidirectional"))
      (node (ref "IC4") (pin "12") (pinfunction "4A_12") (pintype "input"))
      (node (ref "PH46") (pin "7") (pinfunction "7_7") (pintype "passive"))
    )
    (net (code "332") (name "O4B") (class "Default")
      (node (ref "AR2") (pin "4") (pinfunction "4_4") (pintype "bidirectional"))
      (node (ref "IC4") (pin "13") (pinfunction "4B_13") (pintype "input"))
      (node (ref "PH46") (pin "8") (pinfunction "8_8") (pintype "passive"))
    )
    (net (code "333") (name "O4Y") (class "Default")
      (node (ref "IC4") (pin "11") (pinfunction "4Y_11") (pintype "output"))
      (node (ref "PH37") (pin "4") (pinfunction "4_4") (pintype "passive"))
    )
    (net (code "334") (name "OUT_L+") (class "Default")
      (node (ref "IC11") (pin "1") (pinfunction "+OUT_L_1") (pintype "input"))
      (node (ref "PH65") (pin "4") (pinfunction "4_4") (pintype "passive"))
    )
    (net (code "335") (name "OUT_L-") (class "Default")
      (node (ref "IC11") (pin "3") (pinfunction "-OUT_L_3") (pintype "input"))
      (node (ref "PH65") (pin "3") (pinfunction "3_3") (pintype "passive"))
    )
    (net (code "336") (name "OUT_R+") (class "Default")
      (node (ref "IC11") (pin "16") (pinfunction "+OUT_R_16") (pintype "output"))
      (node (ref "PH65") (pin "2") (pinfunction "2_2") (pintype "passive"))
    )
    (net (code "337") (name "OUT_R-") (class "Default")
      (node (ref "IC11") (pin "14") (pinfunction "-OUT_R_14") (pintype "output"))
      (node (ref "PH65") (pin "1") (pinfunction "1_1") (pintype "passive"))
    )
    (net (code "338") (name "R") (class "Default")
      (node (ref "PH11") (pin "1") (pinfunction "1_1") (pintype "passive"))
      (node (ref "R58") (pin "2") (pinfunction "2_2") (pintype "passive"))
    )
    (net (code "339") (name "SA") (class "Default")
      (node (ref "DP1") (pin "10") (pinfunction "10_10") (pintype "bidirectional"))
      (node (ref "R41") (pin "2") (pinfunction "2_2") (pintype "passive"))
    )
    (net (code "340") (name "SA'") (class "Default")
      (node (ref "IC10") (pin "A") (pinfunction "A_A") (pintype "bidirectional"))
      (node (ref "R41") (pin "1") (pinfunction "1_1") (pintype "passive"))
    )
    (net (code "341") (name "SB") (class "Default")
      (node (ref "DP1") (pin "8") (pinfunction "8_8") (pintype "bidirectional"))
      (node (ref "R42") (pin "2") (pinfunction "2_2") (pintype "passive"))
    )
    (net (code "342") (name "SB'") (class "Default")
      (node (ref "IC10") (pin "B") (pinfunction "B_B") (pintype "bidirectional"))
      (node (ref "R42") (pin "1") (pinfunction "1_1") (pintype "passive"))
    )
    (net (code "343") (name "SC") (class "Default")
      (node (ref "DP1") (pin "1") (pinfunction "1_1") (pintype "bidirectional"))
      (node (ref "R43") (pin "2") (pinfunction "2_2") (pintype "passive"))
    )
    (net (code "344") (name "SC'") (class "Default")
      (node (ref "IC10") (pin "C") (pinfunction "C_C") (pintype "bidirectional"))
      (node (ref "R43") (pin "1") (pinfunction "1_1") (pintype "passive"))
    )
    (net (code "345") (name "SD") (class "Default")
      (node (ref "DP1") (pin "5") (pinfunction "5_5") (pintype "bidirectional"))
      (node (ref "R44") (pin "2") (pinfunction "2_2") (pintype "passive"))
    )
    (net (code "346") (name "SD'") (class "Default")
      (node (ref "IC10") (pin "D") (pinfunction "D_D") (pintype "bidirectional"))
      (node (ref "R44") (pin "1") (pinfunction "1_1") (pintype "passive"))
    )
    (net (code "347") (name "SE") (class "Default")
      (node (ref "DP1") (pin "3") (pinfunction "3_3") (pintype "bidirectional"))
      (node (ref "R45") (pin "2") (pinfunction "2_2") (pintype "passive"))
    )
    (net (code "348") (name "SE'") (class "Default")
      (node (ref "IC10") (pin "E") (pinfunction "E_E") (pintype "bidirectional"))
      (node (ref "R45") (pin "1") (pinfunction "1_1") (pintype "passive"))
    )
    (net (code "349") (name "SF") (class "Default")
      (node (ref "DP1") (pin "6") (pinfunction "6_6") (pintype "bidirectional"))
      (node (ref "R46") (pin "2") (pinfunction "2_2") (pintype "passive"))
    )
    (net (code "350") (name "SF'") (class "Default")
      (node (ref "IC10") (pin "F") (pinfunction "F_F") (pintype "bidirectional"))
      (node (ref "R46") (pin "1") (pinfunction "1_1") (pintype "passive"))
    )
    (net (code "351") (name "SG") (class "Default")
      (node (ref "DP1") (pin "7") (pinfunction "7_7") (pintype "bidirectional"))
      (node (ref "R47") (pin "2") (pinfunction "2_2") (pintype "passive"))
    )
    (net (code "352") (name "SG'") (class "Default")
      (node (ref "IC10") (pin "G") (pinfunction "G_G") (pintype "bidirectional"))
      (node (ref "R47") (pin "1") (pinfunction "1_1") (pintype "passive"))
    )
    (net (code "353") (name "SHDN") (class "Default")
      (node (ref "IC11") (pin "12") (pinfunction "SHND_12") (pintype "output"))
    )
    (net (code "354") (name "VCC") (class "Default")
      (node (ref "C23") (pin "1") (pinfunction "1_1") (pintype "passive"))
      (node (ref "C24") (pin "1") (pinfunction "1_1") (pintype "passive"))
      (node (ref "C27") (pin "+") (pinfunction "+_+") (pintype "passive"))
      (node (ref "C34") (pin "1") (pinfunction "1_1") (pintype "passive"))
      (node (ref "F1") (pin "2") (pinfunction "2_2") (pintype "passive"))
      (node (ref "IC1") (pin "4") (pinfunction "VCC_4") (pintype "power_in"))
      (node (ref "IC10") (pin "BI/RBO") (pinfunction "BI/RBO_BI/RBO") (pintype "bidirectional"))
      (node (ref "IC10") (pin "LT") (pinfunction "LT_LT") (pintype "bidirectional"))
      (node (ref "IC10") (pin "VCC") (pinfunction "VCC_VCC") (pintype "bidirectional"))
      (node (ref "IC11") (pin "13") (pinfunction "PVDD1_13") (pintype "output"))
      (node (ref "IC11") (pin "4") (pinfunction "PVDD_4") (pintype "input"))
      (node (ref "IC11") (pin "6") (pinfunction "VDD_6") (pintype "input"))
      (node (ref "IC14") (pin "1") (pinfunction "IN_1") (pintype "input"))
      (node (ref "IC14") (pin "3") (pinfunction "EN_3") (pintype "input"))
      (node (ref "IC2") (pin "4") (pinfunction "VCC_4") (pintype "power_in"))
      (node (ref "IC3") (pin "14") (pinfunction "VCC_14") (pintype "power_in"))
      (node (ref "IC4") (pin "14") (pinfunction "VCC_14") (pintype "power_in"))
      (node (ref "IC5") (pin "14") (pinfunction "VCC_14") (pintype "power_in"))
      (node (ref "IC6") (pin "16") (pinfunction "VDD_16") (pintype "power_in"))
      (node (ref "IC7") (pin "16") (pinfunction "VDD_16") (pintype "power_in"))
      (node (ref "IC8") (pin "4") (pinfunction "R_4") (pintype "input"))
      (node (ref "IC8") (pin "8") (pinfunction "V+_8") (pintype "power_in"))
      (node (ref "PH58") (pin "1") (pinfunction "1_1") (pintype "passive"))
      (node (ref "PH58") (pin "10") (pinfunction "10_10") (pintype "passive"))
      (node (ref "PH58") (pin "11") (pinfunction "11_11") (pintype "passive"))
      (node (ref "PH58") (pin "12") (pinfunction "12_12") (pintype "passive"))
      (node (ref "PH58") (pin "13") (pinfunction "13_13") (pintype "passive"))
      (node (ref "PH58") (pin "14") (pinfunction "14_14") (pintype "passive"))
      (node (ref "PH58") (pin "15") (pinfunction "15_15") (pintype "passive"))
      (node (ref "PH58") (pin "16") (pinfunction "16_16") (pintype "passive"))
      (node (ref "PH58") (pin "17") (pinfunction "17_17") (pintype "passive"))
      (node (ref "PH58") (pin "18") (pinfunction "18_18") (pintype "passive"))
      (node (ref "PH58") (pin "19") (pinfunction "19_19") (pintype "passive"))
      (node (ref "PH58") (pin "2") (pinfunction "2_2") (pintype "passive"))
      (node (ref "PH58") (pin "20") (pinfunction "20_20") (pintype "passive"))
      (node (ref "PH58") (pin "21") (pinfunction "21_21") (pintype "passive"))
      (node (ref "PH58") (pin "22") (pinfunction "22_22") (pintype "passive"))
      (node (ref "PH58") (pin "23") (pinfunction "23_23") (pintype "passive"))
      (node (ref "PH58") (pin "24") (pinfunction "24_24") (pintype "passive"))
      (node (ref "PH58") (pin "25") (pinfunction "25_25") (pintype "passive"))
      (node (ref "PH58") (pin "26") (pinfunction "26_26") (pintype "passive"))
      (node (ref "PH58") (pin "27") (pinfunction "27_27") (pintype "passive"))
      (node (ref "PH58") (pin "28") (pinfunction "28_28") (pintype "passive"))
      (node (ref "PH58") (pin "29") (pinfunction "29_29") (pintype "passive"))
      (node (ref "PH58") (pin "3") (pinfunction "3_3") (pintype "passive"))
      (node (ref "PH58") (pin "30") (pinfunction "30_30") (pintype "passive"))
      (node (ref "PH58") (pin "4") (pinfunction "4_4") (pintype "passive"))
      (node (ref "PH58") (pin "5") (pinfunction "5_5") (pintype "passive"))
      (node (ref "PH58") (pin "6") (pinfunction "6_6") (pintype "passive"))
      (node (ref "PH58") (pin "7") (pinfunction "7_7") (pintype "passive"))
      (node (ref "PH58") (pin "8") (pinfunction "8_8") (pintype "passive"))
      (node (ref "PH58") (pin "9") (pinfunction "9_9") (pintype "passive"))
      (node (ref "R31") (pin "1") (pinfunction "1_1") (pintype "passive"))
      (node (ref "U2") (pin "A1") (pinfunction "A1_A1") (pintype "bidirectional"))
      (node (ref "U2") (pin "HA") (pinfunction "H1_HA") (pintype "bidirectional"))
    )
    (net (code "355") (name "VEXT") (class "Default")
      (node (ref "PH63") (pin "15") (pinfunction "15_15") (pintype "passive"))
      (node (ref "S1") (pin "1") (pinfunction "L1_1") (pintype "passive"))
    )
    (net (code "356") (name "VREF") (class "Default")
      (node (ref "C25") (pin "1") (pinfunction "1_1") (pintype "passive"))
      (node (ref "IC11") (pin "8") (pinfunction "VREF_8") (pintype "input"))
    )
    (net (code "357") (name "VUSB") (class "Default")
      (node (ref "S1") (pin "3") (pinfunction "L2_3") (pintype "passive"))
      (node (ref "U1") (pin "1") (pinfunction "VCC_1") (pintype "bidirectional"))
    )
    (net (code "358") (name "X+") (class "Default")
      (node (ref "C29") (pin "1") (pinfunction "1_1") (pintype "passive"))
      (node (ref "IC13") (pin "5") (pinfunction "XOUT_5") (pintype "bidirectional"))
      (node (ref "PH30") (pin "1") (pinfunction "1_1") (pintype "passive"))
    )
    (net (code "359") (name "Y+") (class "Default")
      (node (ref "C30") (pin "1") (pinfunction "1_1") (pintype "passive"))
      (node (ref "IC13") (pin "4") (pinfunction "YOUT_4") (pintype "bidirectional"))
      (node (ref "PH30") (pin "2") (pinfunction "2_2") (pintype "passive"))
    )
    (net (code "360") (name "Z+") (class "Default")
      (node (ref "C31") (pin "1") (pinfunction "1_1") (pintype "passive"))
      (node (ref "IC13") (pin "16") (pinfunction "ZOUT_16") (pintype "bidirectional"))
      (node (ref "PH30") (pin "3") (pinfunction "3_3") (pintype "passive"))
    )
    (net (code "361") (name "unconnected-(AR3-Pad4)") (class "Default")
      (node (ref "AR3") (pin "4") (pinfunction "4_4") (pintype "bidirectional"))
    )
    (net (code "362") (name "unconnected-(AR3-Pad8)") (class "Default")
      (node (ref "AR3") (pin "8") (pinfunction "8_8") (pintype "bidirectional"))
    )
    (net (code "363") (name "unconnected-(AR4-Pad1)") (class "Default")
      (node (ref "AR4") (pin "1") (pinfunction "1_1") (pintype "bidirectional"))
    )
    (net (code "364") (name "unconnected-(AR4-Pad2)") (class "Default")
      (node (ref "AR4") (pin "2") (pinfunction "2_2") (pintype "bidirectional"))
    )
    (net (code "365") (name "unconnected-(AR4-Pad3)") (class "Default")
      (node (ref "AR4") (pin "3") (pinfunction "3_3") (pintype "bidirectional"))
    )
    (net (code "366") (name "unconnected-(AR4-Pad4)") (class "Default")
      (node (ref "AR4") (pin "4") (pinfunction "4_4") (pintype "bidirectional"))
    )
    (net (code "367") (name "unconnected-(IC13-ST-Pad2)") (class "Default")
      (node (ref "IC13") (pin "2") (pinfunction "ST_2") (pintype "bidirectional"))
    )
    (net (code "368") (name "unconnected-(IC14-BP-Pad4)") (class "Default")
      (node (ref "IC14") (pin "4") (pinfunction "BP_4") (pintype "input"))
    )
    (net (code "369") (name "unconnected-(JC1-Pad4)") (class "Default")
      (node (ref "JC1") (pin "4") (pinfunction "4_4") (pintype "bidirectional"))
    )
    (net (code "370") (name "unconnected-(JC1-Pad5)") (class "Default")
      (node (ref "JC1") (pin "5") (pinfunction "5_5") (pintype "bidirectional"))
    )
    (net (code "371") (name "unconnected-(JC2-Pad4)") (class "Default")
      (node (ref "JC2") (pin "4") (pinfunction "4_4") (pintype "bidirectional"))
    )
    (net (code "372") (name "unconnected-(JC2-Pad5)") (class "Default")
      (node (ref "JC2") (pin "5") (pinfunction "5_5") (pintype "bidirectional"))
    )
    (net (code "373") (name "unconnected-(S1-R1-Pad4)") (class "Default")
      (node (ref "S1") (pin "4") (pinfunction "R1_4") (pintype "passive"))
    )
    (net (code "374") (name "unconnected-(S1-R2-Pad6)") (class "Default")
      (node (ref "S1") (pin "6") (pinfunction "R2_6") (pintype "passive"))
    )
    (net (code "375") (name "unconnected-(S1-RC-Pad5)") (class "Default")
      (node (ref "S1") (pin "5") (pinfunction "RC_5") (pintype "passive"))
    )
    (net (code "376") (name "unconnected-(U1-D+-Pad3)") (class "Default")
      (node (ref "U1") (pin "3") (pinfunction "D+_3") (pintype "bidirectional"))
    )
    (net (code "377") (name "unconnected-(U1-D--Pad2)") (class "Default")
      (node (ref "U1") (pin "2") (pinfunction "D-_2") (pintype "bidirectional"))
    )
    (net (code "378") (name "unconnected-(U1-ID-Pad4)") (class "Default")
      (node (ref "U1") (pin "4") (pinfunction "ID_4") (pintype "bidirectional"))
    )
  )
)
